# uac.net
KiCad netlist of a schematic drawn in EAGLE
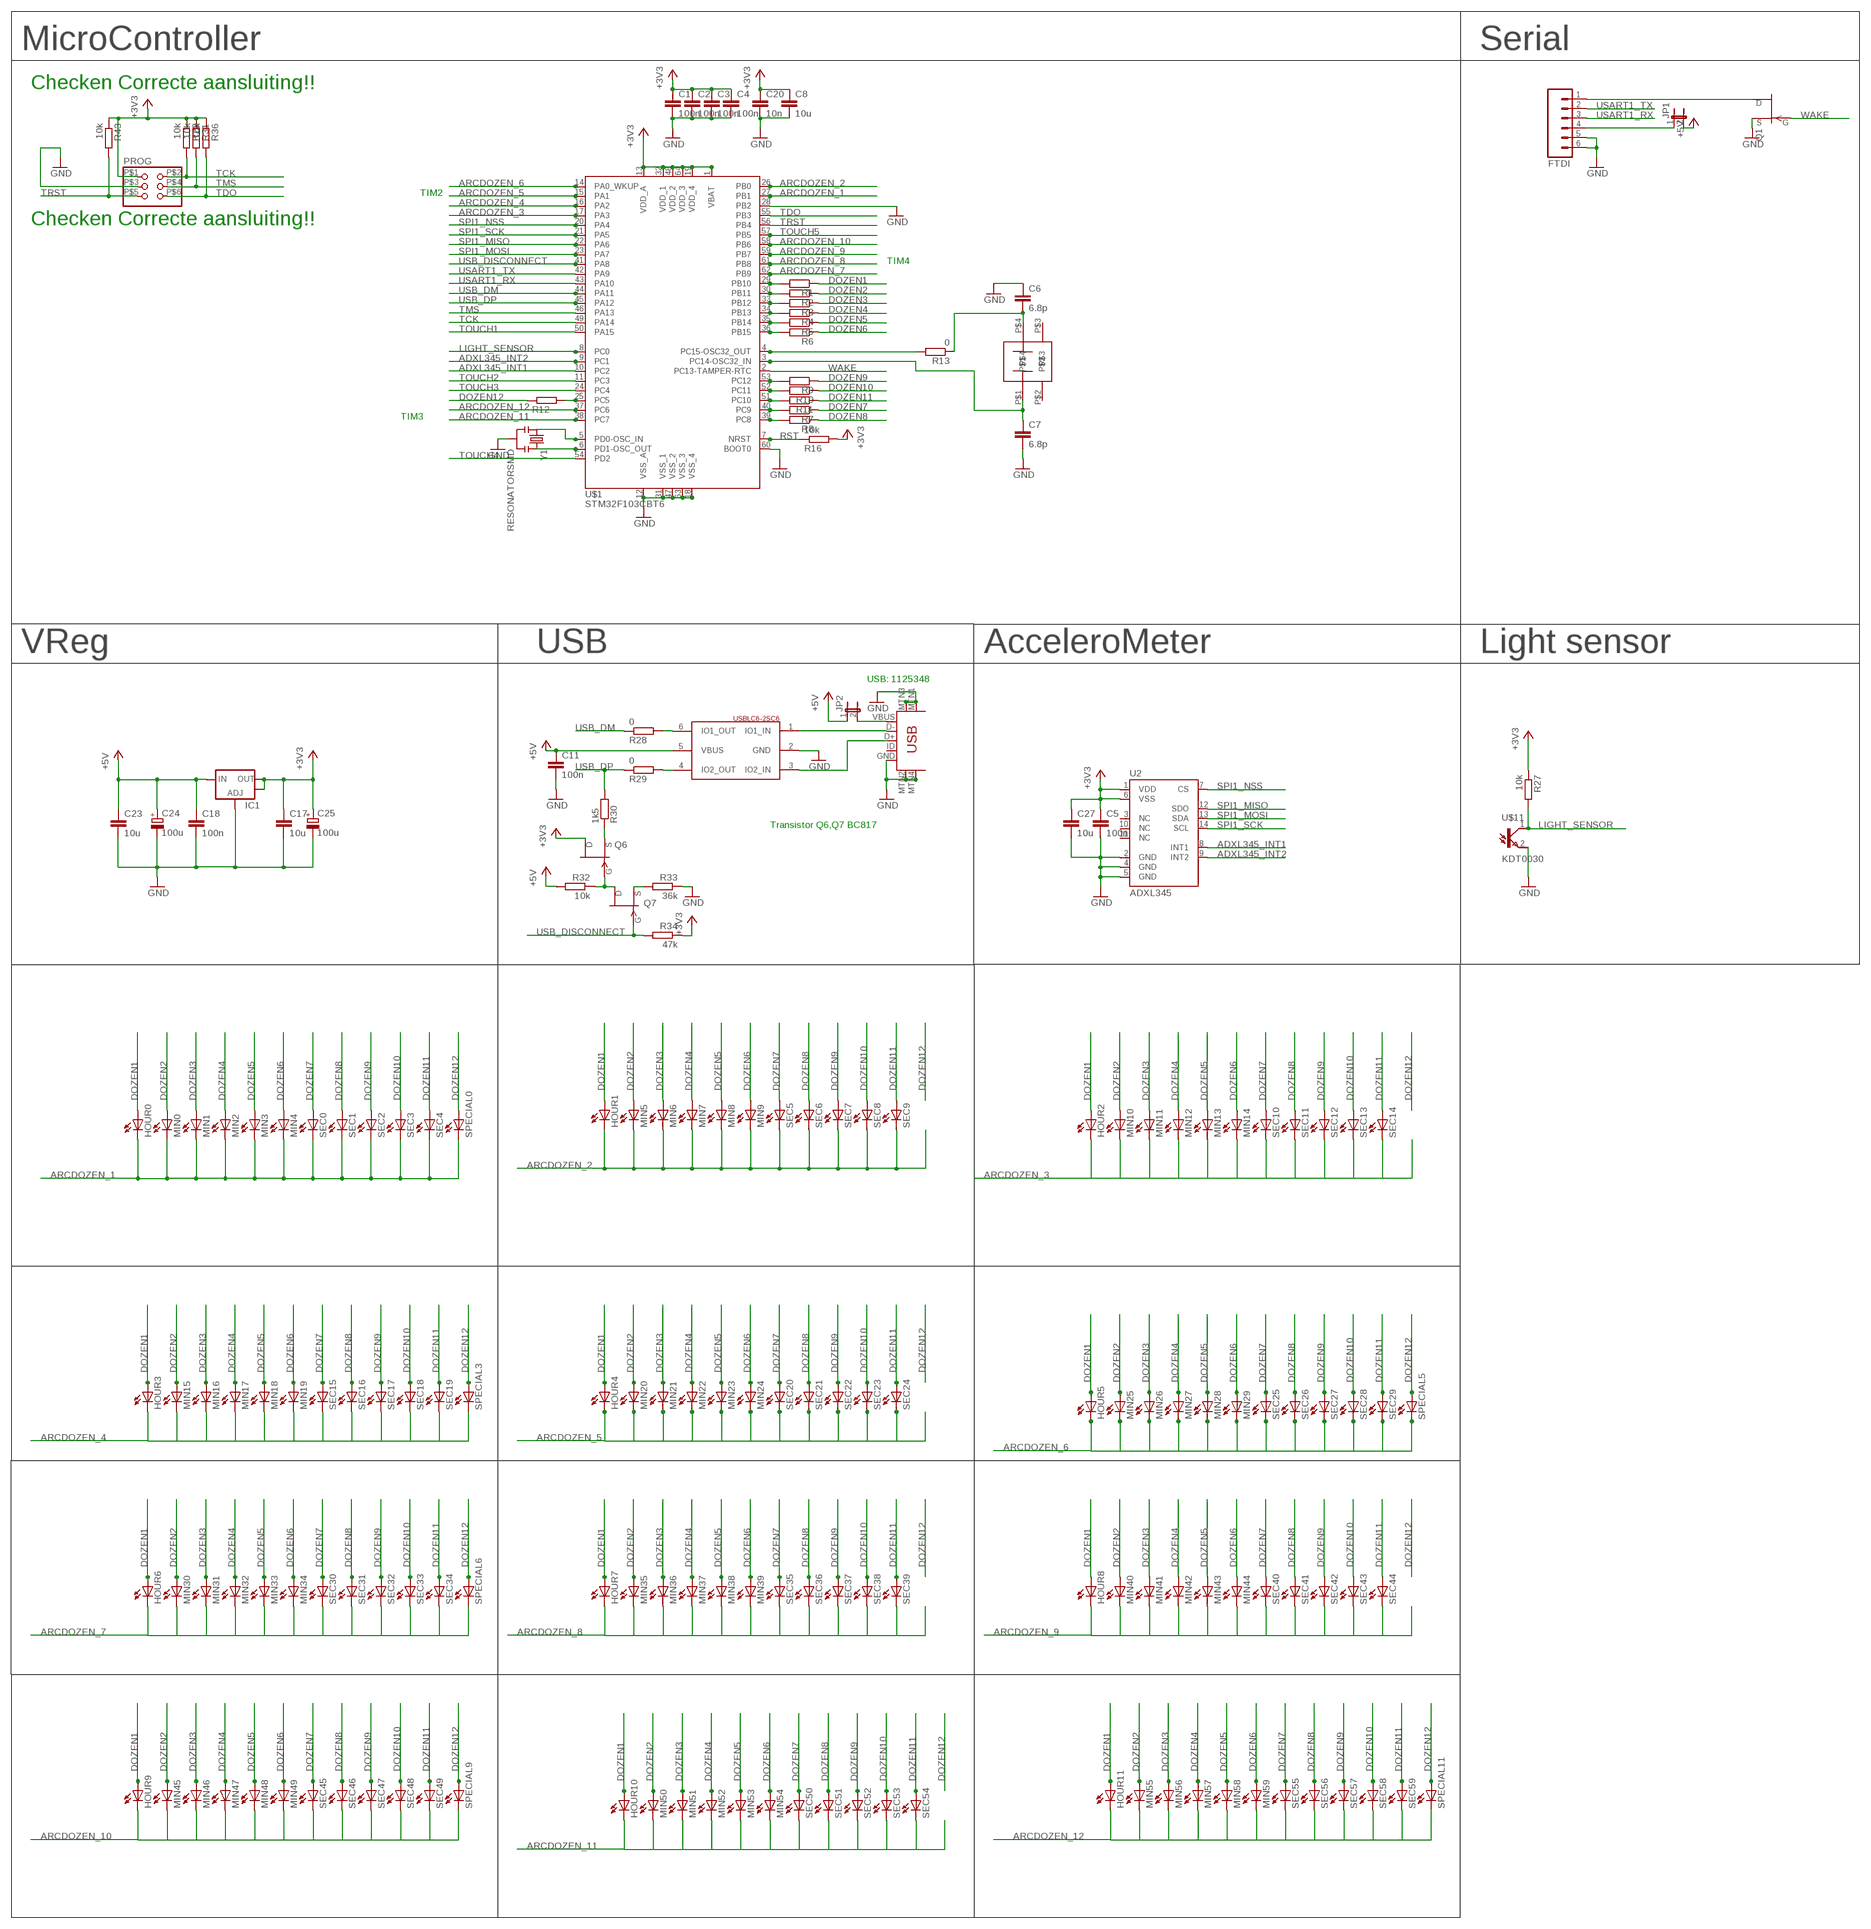
[diagram p0: schematic, sheet 1]

(export (version "E")
  (design (tool "Eeschema 10.0.6"))
  (components
    (comp (ref "C1")
      (value "100n")
      (footprint "eagle-import:C0603")
      (libsource (lib "eagle-import") (part "C-EUC0603"))
    )
    (comp (ref "C2")
      (value "100n")
      (footprint "eagle-import:C0603")
      (libsource (lib "eagle-import") (part "C-EUC0603"))
    )
    (comp (ref "C3")
      (value "100n")
      (footprint "eagle-import:C0603")
      (libsource (lib "eagle-import") (part "C-EUC0603"))
    )
    (comp (ref "C4")
      (value "100n")
      (footprint "eagle-import:C0603")
      (libsource (lib "eagle-import") (part "C-EUC0603"))
    )
    (comp (ref "C5")
      (value "100n")
      (footprint "eagle-import:C0603")
      (libsource (lib "eagle-import") (part "C-EUC0603"))
    )
    (comp (ref "C6")
      (value "6.8p")
      (footprint "eagle-import:C0603")
      (libsource (lib "eagle-import") (part "C-EUC0603"))
    )
    (comp (ref "C7")
      (value "6.8p")
      (footprint "eagle-import:C0603")
      (libsource (lib "eagle-import") (part "C-EUC0603"))
    )
    (comp (ref "C8")
      (value "10u")
      (footprint "eagle-import:C0603")
      (libsource (lib "eagle-import") (part "C-EUC0603"))
    )
    (comp (ref "C11")
      (value "100n")
      (footprint "eagle-import:C0603")
      (libsource (lib "eagle-import") (part "C-EUC0603"))
    )
    (comp (ref "C17")
      (value "10u")
      (footprint "eagle-import:C0603")
      (libsource (lib "eagle-import") (part "C-EUC0603"))
    )
    (comp (ref "C18")
      (value "100n")
      (footprint "eagle-import:C0603")
      (libsource (lib "eagle-import") (part "C-EUC0603"))
    )
    (comp (ref "C20")
      (value "10n")
      (footprint "eagle-import:C0603")
      (libsource (lib "eagle-import") (part "C-EUC0603"))
    )
    (comp (ref "C23")
      (value "10u")
      (footprint "eagle-import:C0603")
      (libsource (lib "eagle-import") (part "C-EUC0603"))
    )
    (comp (ref "C24")
      (value "100u")
      (footprint "eagle-import:SMC_C")
      (libsource (lib "eagle-import") (part "CPOL-EUSMCC"))
    )
    (comp (ref "C25")
      (value "100u")
      (footprint "eagle-import:SMC_C")
      (libsource (lib "eagle-import") (part "CPOL-EUSMCC"))
    )
    (comp (ref "C27")
      (value "10u")
      (footprint "eagle-import:C0603")
      (libsource (lib "eagle-import") (part "C-EUC0603"))
    )
    (comp (ref "FTDI")
      (value "M06SMD")
      (footprint "eagle-import:1X06-SMD")
      (libsource (lib "eagle-import") (part "M06SMD"))
    )
    (comp (ref "HOUR0")
      (value "LEDCHIPLED_0603")
      (footprint "eagle-import:CHIPLED_0603")
      (libsource (lib "eagle-import") (part "LEDCHIPLED_0603"))
    )
    (comp (ref "HOUR1")
      (value "LEDCHIPLED_0603")
      (footprint "eagle-import:CHIPLED_0603")
      (libsource (lib "eagle-import") (part "LEDCHIPLED_0603"))
    )
    (comp (ref "HOUR2")
      (value "LEDCHIPLED_0603")
      (footprint "eagle-import:CHIPLED_0603")
      (libsource (lib "eagle-import") (part "LEDCHIPLED_0603"))
    )
    (comp (ref "HOUR3")
      (value "LEDCHIPLED_0603")
      (footprint "eagle-import:CHIPLED_0603")
      (libsource (lib "eagle-import") (part "LEDCHIPLED_0603"))
    )
    (comp (ref "HOUR4")
      (value "LEDCHIPLED_0603")
      (footprint "eagle-import:CHIPLED_0603")
      (libsource (lib "eagle-import") (part "LEDCHIPLED_0603"))
    )
    (comp (ref "HOUR5")
      (value "LEDCHIPLED_0603")
      (footprint "eagle-import:CHIPLED_0603")
      (libsource (lib "eagle-import") (part "LEDCHIPLED_0603"))
    )
    (comp (ref "HOUR6")
      (value "LEDCHIPLED_0603")
      (footprint "eagle-import:CHIPLED_0603")
      (libsource (lib "eagle-import") (part "LEDCHIPLED_0603"))
    )
    (comp (ref "HOUR7")
      (value "LEDCHIPLED_0603")
      (footprint "eagle-import:CHIPLED_0603")
      (libsource (lib "eagle-import") (part "LEDCHIPLED_0603"))
    )
    (comp (ref "HOUR8")
      (value "LEDCHIPLED_0603")
      (footprint "eagle-import:CHIPLED_0603")
      (libsource (lib "eagle-import") (part "LEDCHIPLED_0603"))
    )
    (comp (ref "HOUR9")
      (value "LEDCHIPLED_0603")
      (footprint "eagle-import:CHIPLED_0603")
      (libsource (lib "eagle-import") (part "LEDCHIPLED_0603"))
    )
    (comp (ref "HOUR10")
      (value "LEDCHIPLED_0603")
      (footprint "eagle-import:CHIPLED_0603")
      (libsource (lib "eagle-import") (part "LEDCHIPLED_0603"))
    )
    (comp (ref "HOUR11")
      (value "LEDCHIPLED_0603")
      (footprint "eagle-import:CHIPLED_0603")
      (libsource (lib "eagle-import") (part "LEDCHIPLED_0603"))
    )
    (comp (ref "IC1")
      (value "V_REG_LM1117SOT223")
      (footprint "eagle-import:SOT223")
      (libsource (lib "eagle-import") (part "V_REG_LM1117SOT223"))
    )
    (comp (ref "JP1")
      (value "JUMPER-2SMD-NO")
      (footprint "eagle-import:SJ_2S-NO")
      (libsource (lib "eagle-import") (part "JUMPER-2SMD-NO"))
    )
    (comp (ref "JP2")
      (value "JUMPER-2SMD-NO")
      (footprint "eagle-import:SJ_2S-NO")
      (libsource (lib "eagle-import") (part "JUMPER-2SMD-NO"))
    )
    (comp (ref "MIN0")
      (value "LEDCHIPLED_0603")
      (footprint "eagle-import:CHIPLED_0603")
      (libsource (lib "eagle-import") (part "LEDCHIPLED_0603"))
    )
    (comp (ref "MIN1")
      (value "LEDCHIPLED_0603")
      (footprint "eagle-import:CHIPLED_0603")
      (libsource (lib "eagle-import") (part "LEDCHIPLED_0603"))
    )
    (comp (ref "MIN2")
      (value "LEDCHIPLED_0603")
      (footprint "eagle-import:CHIPLED_0603")
      (libsource (lib "eagle-import") (part "LEDCHIPLED_0603"))
    )
    (comp (ref "MIN3")
      (value "LEDCHIPLED_0603")
      (footprint "eagle-import:CHIPLED_0603")
      (libsource (lib "eagle-import") (part "LEDCHIPLED_0603"))
    )
    (comp (ref "MIN4")
      (value "LEDCHIPLED_0603")
      (footprint "eagle-import:CHIPLED_0603")
      (libsource (lib "eagle-import") (part "LEDCHIPLED_0603"))
    )
    (comp (ref "MIN5")
      (value "LEDCHIPLED_0603")
      (footprint "eagle-import:CHIPLED_0603")
      (libsource (lib "eagle-import") (part "LEDCHIPLED_0603"))
    )
    (comp (ref "MIN6")
      (value "LEDCHIPLED_0603")
      (footprint "eagle-import:CHIPLED_0603")
      (libsource (lib "eagle-import") (part "LEDCHIPLED_0603"))
    )
    (comp (ref "MIN7")
      (value "LEDCHIPLED_0603")
      (footprint "eagle-import:CHIPLED_0603")
      (libsource (lib "eagle-import") (part "LEDCHIPLED_0603"))
    )
    (comp (ref "MIN8")
      (value "LEDCHIPLED_0603")
      (footprint "eagle-import:CHIPLED_0603")
      (libsource (lib "eagle-import") (part "LEDCHIPLED_0603"))
    )
    (comp (ref "MIN9")
      (value "LEDCHIPLED_0603")
      (footprint "eagle-import:CHIPLED_0603")
      (libsource (lib "eagle-import") (part "LEDCHIPLED_0603"))
    )
    (comp (ref "MIN10")
      (value "LEDCHIPLED_0603")
      (footprint "eagle-import:CHIPLED_0603")
      (libsource (lib "eagle-import") (part "LEDCHIPLED_0603"))
    )
    (comp (ref "MIN11")
      (value "LEDCHIPLED_0603")
      (footprint "eagle-import:CHIPLED_0603")
      (libsource (lib "eagle-import") (part "LEDCHIPLED_0603"))
    )
    (comp (ref "MIN12")
      (value "LEDCHIPLED_0603")
      (footprint "eagle-import:CHIPLED_0603")
      (libsource (lib "eagle-import") (part "LEDCHIPLED_0603"))
    )
    (comp (ref "MIN13")
      (value "LEDCHIPLED_0603")
      (footprint "eagle-import:CHIPLED_0603")
      (libsource (lib "eagle-import") (part "LEDCHIPLED_0603"))
    )
    (comp (ref "MIN14")
      (value "LEDCHIPLED_0603")
      (footprint "eagle-import:CHIPLED_0603")
      (libsource (lib "eagle-import") (part "LEDCHIPLED_0603"))
    )
    (comp (ref "MIN15")
      (value "LEDCHIPLED_0603")
      (footprint "eagle-import:CHIPLED_0603")
      (libsource (lib "eagle-import") (part "LEDCHIPLED_0603"))
    )
    (comp (ref "MIN16")
      (value "LEDCHIPLED_0603")
      (footprint "eagle-import:CHIPLED_0603")
      (libsource (lib "eagle-import") (part "LEDCHIPLED_0603"))
    )
    (comp (ref "MIN17")
      (value "LEDCHIPLED_0603")
      (footprint "eagle-import:CHIPLED_0603")
      (libsource (lib "eagle-import") (part "LEDCHIPLED_0603"))
    )
    (comp (ref "MIN18")
      (value "LEDCHIPLED_0603")
      (footprint "eagle-import:CHIPLED_0603")
      (libsource (lib "eagle-import") (part "LEDCHIPLED_0603"))
    )
    (comp (ref "MIN19")
      (value "LEDCHIPLED_0603")
      (footprint "eagle-import:CHIPLED_0603")
      (libsource (lib "eagle-import") (part "LEDCHIPLED_0603"))
    )
    (comp (ref "MIN20")
      (value "LEDCHIPLED_0603")
      (footprint "eagle-import:CHIPLED_0603")
      (libsource (lib "eagle-import") (part "LEDCHIPLED_0603"))
    )
    (comp (ref "MIN21")
      (value "LEDCHIPLED_0603")
      (footprint "eagle-import:CHIPLED_0603")
      (libsource (lib "eagle-import") (part "LEDCHIPLED_0603"))
    )
    (comp (ref "MIN22")
      (value "LEDCHIPLED_0603")
      (footprint "eagle-import:CHIPLED_0603")
      (libsource (lib "eagle-import") (part "LEDCHIPLED_0603"))
    )
    (comp (ref "MIN23")
      (value "LEDCHIPLED_0603")
      (footprint "eagle-import:CHIPLED_0603")
      (libsource (lib "eagle-import") (part "LEDCHIPLED_0603"))
    )
    (comp (ref "MIN24")
      (value "LEDCHIPLED_0603")
      (footprint "eagle-import:CHIPLED_0603")
      (libsource (lib "eagle-import") (part "LEDCHIPLED_0603"))
    )
    (comp (ref "MIN25")
      (value "LEDCHIPLED_0603")
      (footprint "eagle-import:CHIPLED_0603")
      (libsource (lib "eagle-import") (part "LEDCHIPLED_0603"))
    )
    (comp (ref "MIN26")
      (value "LEDCHIPLED_0603")
      (footprint "eagle-import:CHIPLED_0603")
      (libsource (lib "eagle-import") (part "LEDCHIPLED_0603"))
    )
    (comp (ref "MIN27")
      (value "LEDCHIPLED_0603")
      (footprint "eagle-import:CHIPLED_0603")
      (libsource (lib "eagle-import") (part "LEDCHIPLED_0603"))
    )
    (comp (ref "MIN28")
      (value "LEDCHIPLED_0603")
      (footprint "eagle-import:CHIPLED_0603")
      (libsource (lib "eagle-import") (part "LEDCHIPLED_0603"))
    )
    (comp (ref "MIN29")
      (value "LEDCHIPLED_0603")
      (footprint "eagle-import:CHIPLED_0603")
      (libsource (lib "eagle-import") (part "LEDCHIPLED_0603"))
    )
    (comp (ref "MIN30")
      (value "LEDCHIPLED_0603")
      (footprint "eagle-import:CHIPLED_0603")
      (libsource (lib "eagle-import") (part "LEDCHIPLED_0603"))
    )
    (comp (ref "MIN31")
      (value "LEDCHIPLED_0603")
      (footprint "eagle-import:CHIPLED_0603")
      (libsource (lib "eagle-import") (part "LEDCHIPLED_0603"))
    )
    (comp (ref "MIN32")
      (value "LEDCHIPLED_0603")
      (footprint "eagle-import:CHIPLED_0603")
      (libsource (lib "eagle-import") (part "LEDCHIPLED_0603"))
    )
    (comp (ref "MIN33")
      (value "LEDCHIPLED_0603")
      (footprint "eagle-import:CHIPLED_0603")
      (libsource (lib "eagle-import") (part "LEDCHIPLED_0603"))
    )
    (comp (ref "MIN34")
      (value "LEDCHIPLED_0603")
      (footprint "eagle-import:CHIPLED_0603")
      (libsource (lib "eagle-import") (part "LEDCHIPLED_0603"))
    )
    (comp (ref "MIN35")
      (value "LEDCHIPLED_0603")
      (footprint "eagle-import:CHIPLED_0603")
      (libsource (lib "eagle-import") (part "LEDCHIPLED_0603"))
    )
    (comp (ref "MIN36")
      (value "LEDCHIPLED_0603")
      (footprint "eagle-import:CHIPLED_0603")
      (libsource (lib "eagle-import") (part "LEDCHIPLED_0603"))
    )
    (comp (ref "MIN37")
      (value "LEDCHIPLED_0603")
      (footprint "eagle-import:CHIPLED_0603")
      (libsource (lib "eagle-import") (part "LEDCHIPLED_0603"))
    )
    (comp (ref "MIN38")
      (value "LEDCHIPLED_0603")
      (footprint "eagle-import:CHIPLED_0603")
      (libsource (lib "eagle-import") (part "LEDCHIPLED_0603"))
    )
    (comp (ref "MIN39")
      (value "LEDCHIPLED_0603")
      (footprint "eagle-import:CHIPLED_0603")
      (libsource (lib "eagle-import") (part "LEDCHIPLED_0603"))
    )
    (comp (ref "MIN40")
      (value "LEDCHIPLED_0603")
      (footprint "eagle-import:CHIPLED_0603")
      (libsource (lib "eagle-import") (part "LEDCHIPLED_0603"))
    )
    (comp (ref "MIN41")
      (value "LEDCHIPLED_0603")
      (footprint "eagle-import:CHIPLED_0603")
      (libsource (lib "eagle-import") (part "LEDCHIPLED_0603"))
    )
    (comp (ref "MIN42")
      (value "LEDCHIPLED_0603")
      (footprint "eagle-import:CHIPLED_0603")
      (libsource (lib "eagle-import") (part "LEDCHIPLED_0603"))
    )
    (comp (ref "MIN43")
      (value "LEDCHIPLED_0603")
      (footprint "eagle-import:CHIPLED_0603")
      (libsource (lib "eagle-import") (part "LEDCHIPLED_0603"))
    )
    (comp (ref "MIN44")
      (value "LEDCHIPLED_0603")
      (footprint "eagle-import:CHIPLED_0603")
      (libsource (lib "eagle-import") (part "LEDCHIPLED_0603"))
    )
    (comp (ref "MIN45")
      (value "LEDCHIPLED_0603")
      (footprint "eagle-import:CHIPLED_0603")
      (libsource (lib "eagle-import") (part "LEDCHIPLED_0603"))
    )
    (comp (ref "MIN46")
      (value "LEDCHIPLED_0603")
      (footprint "eagle-import:CHIPLED_0603")
      (libsource (lib "eagle-import") (part "LEDCHIPLED_0603"))
    )
    (comp (ref "MIN47")
      (value "LEDCHIPLED_0603")
      (footprint "eagle-import:CHIPLED_0603")
      (libsource (lib "eagle-import") (part "LEDCHIPLED_0603"))
    )
    (comp (ref "MIN48")
      (value "LEDCHIPLED_0603")
      (footprint "eagle-import:CHIPLED_0603")
      (libsource (lib "eagle-import") (part "LEDCHIPLED_0603"))
    )
    (comp (ref "MIN49")
      (value "LEDCHIPLED_0603")
      (footprint "eagle-import:CHIPLED_0603")
      (libsource (lib "eagle-import") (part "LEDCHIPLED_0603"))
    )
    (comp (ref "MIN50")
      (value "LEDCHIPLED_0603")
      (footprint "eagle-import:CHIPLED_0603")
      (libsource (lib "eagle-import") (part "LEDCHIPLED_0603"))
    )
    (comp (ref "MIN51")
      (value "LEDCHIPLED_0603")
      (footprint "eagle-import:CHIPLED_0603")
      (libsource (lib "eagle-import") (part "LEDCHIPLED_0603"))
    )
    (comp (ref "MIN52")
      (value "LEDCHIPLED_0603")
      (footprint "eagle-import:CHIPLED_0603")
      (libsource (lib "eagle-import") (part "LEDCHIPLED_0603"))
    )
    (comp (ref "MIN53")
      (value "LEDCHIPLED_0603")
      (footprint "eagle-import:CHIPLED_0603")
      (libsource (lib "eagle-import") (part "LEDCHIPLED_0603"))
    )
    (comp (ref "MIN54")
      (value "LEDCHIPLED_0603")
      (footprint "eagle-import:CHIPLED_0603")
      (libsource (lib "eagle-import") (part "LEDCHIPLED_0603"))
    )
    (comp (ref "MIN55")
      (value "LEDCHIPLED_0603")
      (footprint "eagle-import:CHIPLED_0603")
      (libsource (lib "eagle-import") (part "LEDCHIPLED_0603"))
    )
    (comp (ref "MIN56")
      (value "LEDCHIPLED_0603")
      (footprint "eagle-import:CHIPLED_0603")
      (libsource (lib "eagle-import") (part "LEDCHIPLED_0603"))
    )
    (comp (ref "MIN57")
      (value "LEDCHIPLED_0603")
      (footprint "eagle-import:CHIPLED_0603")
      (libsource (lib "eagle-import") (part "LEDCHIPLED_0603"))
    )
    (comp (ref "MIN58")
      (value "LEDCHIPLED_0603")
      (footprint "eagle-import:CHIPLED_0603")
      (libsource (lib "eagle-import") (part "LEDCHIPLED_0603"))
    )
    (comp (ref "MIN59")
      (value "LEDCHIPLED_0603")
      (footprint "eagle-import:CHIPLED_0603")
      (libsource (lib "eagle-import") (part "LEDCHIPLED_0603"))
    )
    (comp (ref "PROG")
      (value "PINHD-2X3SMT")
      (footprint "eagle-import:2X03_SMT")
      (libsource (lib "eagle-import") (part "PINHD-2X3SMT"))
    )
    (comp (ref "Q1")
      (value "2N7002CK4SST")
      (footprint "eagle-import:SOT23")
      (libsource (lib "eagle-import") (part "2N7002CKSST4"))
    )
    (comp (ref "Q6")
      (value "2N7002CK4SST")
      (footprint "eagle-import:SOT23")
      (libsource (lib "eagle-import") (part "2N7002CKSST4"))
    )
    (comp (ref "Q7")
      (value "2N7002CK4SST")
      (footprint "eagle-import:SOT23")
      (libsource (lib "eagle-import") (part "2N7002CKSST4"))
    )
    (comp (ref "R1")
      (value "R-EU_R0603")
      (footprint "eagle-import:R0603")
      (libsource (lib "eagle-import") (part "R-EU_R0603"))
    )
    (comp (ref "R2")
      (value "R-EU_R0603")
      (footprint "eagle-import:R0603")
      (libsource (lib "eagle-import") (part "R-EU_R0603"))
    )
    (comp (ref "R3")
      (value "R-EU_R0603")
      (footprint "eagle-import:R0603")
      (libsource (lib "eagle-import") (part "R-EU_R0603"))
    )
    (comp (ref "R4")
      (value "R-EU_R0603")
      (footprint "eagle-import:R0603")
      (libsource (lib "eagle-import") (part "R-EU_R0603"))
    )
    (comp (ref "R5")
      (value "R-EU_R0603")
      (footprint "eagle-import:R0603")
      (libsource (lib "eagle-import") (part "R-EU_R0603"))
    )
    (comp (ref "R6")
      (value "R-EU_R0603")
      (footprint "eagle-import:R0603")
      (libsource (lib "eagle-import") (part "R-EU_R0603"))
    )
    (comp (ref "R7")
      (value "R-EU_R0603")
      (footprint "eagle-import:R0603")
      (libsource (lib "eagle-import") (part "R-EU_R0603"))
    )
    (comp (ref "R8")
      (value "R-EU_R0603")
      (footprint "eagle-import:R0603")
      (libsource (lib "eagle-import") (part "R-EU_R0603"))
    )
    (comp (ref "R9")
      (value "R-EU_R0603")
      (footprint "eagle-import:R0603")
      (libsource (lib "eagle-import") (part "R-EU_R0603"))
    )
    (comp (ref "R10")
      (value "R-EU_R0603")
      (footprint "eagle-import:R0603")
      (libsource (lib "eagle-import") (part "R-EU_R0603"))
    )
    (comp (ref "R11")
      (value "R-EU_R0603")
      (footprint "eagle-import:R0603")
      (libsource (lib "eagle-import") (part "R-EU_R0603"))
    )
    (comp (ref "R12")
      (value "R-EU_R0603")
      (footprint "eagle-import:R0603")
      (libsource (lib "eagle-import") (part "R-EU_R0603"))
    )
    (comp (ref "R13")
      (value "0")
      (footprint "eagle-import:R0603")
      (libsource (lib "eagle-import") (part "R-EU_R0603"))
    )
    (comp (ref "R16")
      (value "10k")
      (footprint "eagle-import:R0603")
      (libsource (lib "eagle-import") (part "R-EU_R0603"))
    )
    (comp (ref "R23")
      (value "10k")
      (footprint "eagle-import:R0603")
      (libsource (lib "eagle-import") (part "R-EU_R0603"))
    )
    (comp (ref "R27")
      (value "10k")
      (footprint "eagle-import:R0603")
      (libsource (lib "eagle-import") (part "R-EU_R0603"))
    )
    (comp (ref "R28")
      (value "0")
      (footprint "eagle-import:R0603")
      (libsource (lib "eagle-import") (part "R-EU_R0603"))
    )
    (comp (ref "R29")
      (value "0")
      (footprint "eagle-import:R0603")
      (libsource (lib "eagle-import") (part "R-EU_R0603"))
    )
    (comp (ref "R30")
      (value "1k5")
      (footprint "eagle-import:R0603")
      (libsource (lib "eagle-import") (part "R-EU_R0603"))
    )
    (comp (ref "R31")
      (value "10k")
      (footprint "eagle-import:R0603")
      (libsource (lib "eagle-import") (part "R-EU_R0603"))
    )
    (comp (ref "R32")
      (value "10k")
      (footprint "eagle-import:R0603")
      (libsource (lib "eagle-import") (part "R-EU_R0603"))
    )
    (comp (ref "R33")
      (value "36k")
      (footprint "eagle-import:R0603")
      (libsource (lib "eagle-import") (part "R-EU_R0603"))
    )
    (comp (ref "R34")
      (value "47k")
      (footprint "eagle-import:R0603")
      (libsource (lib "eagle-import") (part "R-EU_R0603"))
    )
    (comp (ref "R36")
      (value "10k")
      (footprint "eagle-import:R0603")
      (libsource (lib "eagle-import") (part "R-EU_R0603"))
    )
    (comp (ref "R43")
      (value "10k")
      (footprint "eagle-import:R0603")
      (libsource (lib "eagle-import") (part "R-EU_R0603"))
    )
    (comp (ref "SEC0")
      (value "LEDCHIPLED_0603")
      (footprint "eagle-import:CHIPLED_0603")
      (libsource (lib "eagle-import") (part "LEDCHIPLED_0603"))
    )
    (comp (ref "SEC1")
      (value "LEDCHIPLED_0603")
      (footprint "eagle-import:CHIPLED_0603")
      (libsource (lib "eagle-import") (part "LEDCHIPLED_0603"))
    )
    (comp (ref "SEC2")
      (value "LEDCHIPLED_0603")
      (footprint "eagle-import:CHIPLED_0603")
      (libsource (lib "eagle-import") (part "LEDCHIPLED_0603"))
    )
    (comp (ref "SEC3")
      (value "LEDCHIPLED_0603")
      (footprint "eagle-import:CHIPLED_0603")
      (libsource (lib "eagle-import") (part "LEDCHIPLED_0603"))
    )
    (comp (ref "SEC4")
      (value "LEDCHIPLED_0603")
      (footprint "eagle-import:CHIPLED_0603")
      (libsource (lib "eagle-import") (part "LEDCHIPLED_0603"))
    )
    (comp (ref "SEC5")
      (value "LEDCHIPLED_0603")
      (footprint "eagle-import:CHIPLED_0603")
      (libsource (lib "eagle-import") (part "LEDCHIPLED_0603"))
    )
    (comp (ref "SEC6")
      (value "LEDCHIPLED_0603")
      (footprint "eagle-import:CHIPLED_0603")
      (libsource (lib "eagle-import") (part "LEDCHIPLED_0603"))
    )
    (comp (ref "SEC7")
      (value "LEDCHIPLED_0603")
      (footprint "eagle-import:CHIPLED_0603")
      (libsource (lib "eagle-import") (part "LEDCHIPLED_0603"))
    )
    (comp (ref "SEC8")
      (value "LEDCHIPLED_0603")
      (footprint "eagle-import:CHIPLED_0603")
      (libsource (lib "eagle-import") (part "LEDCHIPLED_0603"))
    )
    (comp (ref "SEC9")
      (value "LEDCHIPLED_0603")
      (footprint "eagle-import:CHIPLED_0603")
      (libsource (lib "eagle-import") (part "LEDCHIPLED_0603"))
    )
    (comp (ref "SEC10")
      (value "LEDCHIPLED_0603")
      (footprint "eagle-import:CHIPLED_0603")
      (libsource (lib "eagle-import") (part "LEDCHIPLED_0603"))
    )
    (comp (ref "SEC11")
      (value "LEDCHIPLED_0603")
      (footprint "eagle-import:CHIPLED_0603")
      (libsource (lib "eagle-import") (part "LEDCHIPLED_0603"))
    )
    (comp (ref "SEC12")
      (value "LEDCHIPLED_0603")
      (footprint "eagle-import:CHIPLED_0603")
      (libsource (lib "eagle-import") (part "LEDCHIPLED_0603"))
    )
    (comp (ref "SEC13")
      (value "LEDCHIPLED_0603")
      (footprint "eagle-import:CHIPLED_0603")
      (libsource (lib "eagle-import") (part "LEDCHIPLED_0603"))
    )
    (comp (ref "SEC14")
      (value "LEDCHIPLED_0603")
      (footprint "eagle-import:CHIPLED_0603")
      (libsource (lib "eagle-import") (part "LEDCHIPLED_0603"))
    )
    (comp (ref "SEC15")
      (value "LEDCHIPLED_0603")
      (footprint "eagle-import:CHIPLED_0603")
      (libsource (lib "eagle-import") (part "LEDCHIPLED_0603"))
    )
    (comp (ref "SEC16")
      (value "LEDCHIPLED_0603")
      (footprint "eagle-import:CHIPLED_0603")
      (libsource (lib "eagle-import") (part "LEDCHIPLED_0603"))
    )
    (comp (ref "SEC17")
      (value "LEDCHIPLED_0603")
      (footprint "eagle-import:CHIPLED_0603")
      (libsource (lib "eagle-import") (part "LEDCHIPLED_0603"))
    )
    (comp (ref "SEC18")
      (value "LEDCHIPLED_0603")
      (footprint "eagle-import:CHIPLED_0603")
      (libsource (lib "eagle-import") (part "LEDCHIPLED_0603"))
    )
    (comp (ref "SEC19")
      (value "LEDCHIPLED_0603")
      (footprint "eagle-import:CHIPLED_0603")
      (libsource (lib "eagle-import") (part "LEDCHIPLED_0603"))
    )
    (comp (ref "SEC20")
      (value "LEDCHIPLED_0603")
      (footprint "eagle-import:CHIPLED_0603")
      (libsource (lib "eagle-import") (part "LEDCHIPLED_0603"))
    )
    (comp (ref "SEC21")
      (value "LEDCHIPLED_0603")
      (footprint "eagle-import:CHIPLED_0603")
      (libsource (lib "eagle-import") (part "LEDCHIPLED_0603"))
    )
    (comp (ref "SEC22")
      (value "LEDCHIPLED_0603")
      (footprint "eagle-import:CHIPLED_0603")
      (libsource (lib "eagle-import") (part "LEDCHIPLED_0603"))
    )
    (comp (ref "SEC23")
      (value "LEDCHIPLED_0603")
      (footprint "eagle-import:CHIPLED_0603")
      (libsource (lib "eagle-import") (part "LEDCHIPLED_0603"))
    )
    (comp (ref "SEC24")
      (value "LEDCHIPLED_0603")
      (footprint "eagle-import:CHIPLED_0603")
      (libsource (lib "eagle-import") (part "LEDCHIPLED_0603"))
    )
    (comp (ref "SEC25")
      (value "LEDCHIPLED_0603")
      (footprint "eagle-import:CHIPLED_0603")
      (libsource (lib "eagle-import") (part "LEDCHIPLED_0603"))
    )
    (comp (ref "SEC26")
      (value "LEDCHIPLED_0603")
      (footprint "eagle-import:CHIPLED_0603")
      (libsource (lib "eagle-import") (part "LEDCHIPLED_0603"))
    )
    (comp (ref "SEC27")
      (value "LEDCHIPLED_0603")
      (footprint "eagle-import:CHIPLED_0603")
      (libsource (lib "eagle-import") (part "LEDCHIPLED_0603"))
    )
    (comp (ref "SEC28")
      (value "LEDCHIPLED_0603")
      (footprint "eagle-import:CHIPLED_0603")
      (libsource (lib "eagle-import") (part "LEDCHIPLED_0603"))
    )
    (comp (ref "SEC29")
      (value "LEDCHIPLED_0603")
      (footprint "eagle-import:CHIPLED_0603")
      (libsource (lib "eagle-import") (part "LEDCHIPLED_0603"))
    )
    (comp (ref "SEC30")
      (value "LEDCHIPLED_0603")
      (footprint "eagle-import:CHIPLED_0603")
      (libsource (lib "eagle-import") (part "LEDCHIPLED_0603"))
    )
    (comp (ref "SEC31")
      (value "LEDCHIPLED_0603")
      (footprint "eagle-import:CHIPLED_0603")
      (libsource (lib "eagle-import") (part "LEDCHIPLED_0603"))
    )
    (comp (ref "SEC32")
      (value "LEDCHIPLED_0603")
      (footprint "eagle-import:CHIPLED_0603")
      (libsource (lib "eagle-import") (part "LEDCHIPLED_0603"))
    )
    (comp (ref "SEC33")
      (value "LEDCHIPLED_0603")
      (footprint "eagle-import:CHIPLED_0603")
      (libsource (lib "eagle-import") (part "LEDCHIPLED_0603"))
    )
    (comp (ref "SEC34")
      (value "LEDCHIPLED_0603")
      (footprint "eagle-import:CHIPLED_0603")
      (libsource (lib "eagle-import") (part "LEDCHIPLED_0603"))
    )
    (comp (ref "SEC35")
      (value "LEDCHIPLED_0603")
      (footprint "eagle-import:CHIPLED_0603")
      (libsource (lib "eagle-import") (part "LEDCHIPLED_0603"))
    )
    (comp (ref "SEC36")
      (value "LEDCHIPLED_0603")
      (footprint "eagle-import:CHIPLED_0603")
      (libsource (lib "eagle-import") (part "LEDCHIPLED_0603"))
    )
    (comp (ref "SEC37")
      (value "LEDCHIPLED_0603")
      (footprint "eagle-import:CHIPLED_0603")
      (libsource (lib "eagle-import") (part "LEDCHIPLED_0603"))
    )
    (comp (ref "SEC38")
      (value "LEDCHIPLED_0603")
      (footprint "eagle-import:CHIPLED_0603")
      (libsource (lib "eagle-import") (part "LEDCHIPLED_0603"))
    )
    (comp (ref "SEC39")
      (value "LEDCHIPLED_0603")
      (footprint "eagle-import:CHIPLED_0603")
      (libsource (lib "eagle-import") (part "LEDCHIPLED_0603"))
    )
    (comp (ref "SEC40")
      (value "LEDCHIPLED_0603")
      (footprint "eagle-import:CHIPLED_0603")
      (libsource (lib "eagle-import") (part "LEDCHIPLED_0603"))
    )
    (comp (ref "SEC41")
      (value "LEDCHIPLED_0603")
      (footprint "eagle-import:CHIPLED_0603")
      (libsource (lib "eagle-import") (part "LEDCHIPLED_0603"))
    )
    (comp (ref "SEC42")
      (value "LEDCHIPLED_0603")
      (footprint "eagle-import:CHIPLED_0603")
      (libsource (lib "eagle-import") (part "LEDCHIPLED_0603"))
    )
    (comp (ref "SEC43")
      (value "LEDCHIPLED_0603")
      (footprint "eagle-import:CHIPLED_0603")
      (libsource (lib "eagle-import") (part "LEDCHIPLED_0603"))
    )
    (comp (ref "SEC44")
      (value "LEDCHIPLED_0603")
      (footprint "eagle-import:CHIPLED_0603")
      (libsource (lib "eagle-import") (part "LEDCHIPLED_0603"))
    )
    (comp (ref "SEC45")
      (value "LEDCHIPLED_0603")
      (footprint "eagle-import:CHIPLED_0603")
      (libsource (lib "eagle-import") (part "LEDCHIPLED_0603"))
    )
    (comp (ref "SEC46")
      (value "LEDCHIPLED_0603")
      (footprint "eagle-import:CHIPLED_0603")
      (libsource (lib "eagle-import") (part "LEDCHIPLED_0603"))
    )
    (comp (ref "SEC47")
      (value "LEDCHIPLED_0603")
      (footprint "eagle-import:CHIPLED_0603")
      (libsource (lib "eagle-import") (part "LEDCHIPLED_0603"))
    )
    (comp (ref "SEC48")
      (value "LEDCHIPLED_0603")
      (footprint "eagle-import:CHIPLED_0603")
      (libsource (lib "eagle-import") (part "LEDCHIPLED_0603"))
    )
    (comp (ref "SEC49")
      (value "LEDCHIPLED_0603")
      (footprint "eagle-import:CHIPLED_0603")
      (libsource (lib "eagle-import") (part "LEDCHIPLED_0603"))
    )
    (comp (ref "SEC50")
      (value "LEDCHIPLED_0603")
      (footprint "eagle-import:CHIPLED_0603")
      (libsource (lib "eagle-import") (part "LEDCHIPLED_0603"))
    )
    (comp (ref "SEC51")
      (value "LEDCHIPLED_0603")
      (footprint "eagle-import:CHIPLED_0603")
      (libsource (lib "eagle-import") (part "LEDCHIPLED_0603"))
    )
    (comp (ref "SEC52")
      (value "LEDCHIPLED_0603")
      (footprint "eagle-import:CHIPLED_0603")
      (libsource (lib "eagle-import") (part "LEDCHIPLED_0603"))
    )
    (comp (ref "SEC53")
      (value "LEDCHIPLED_0603")
      (footprint "eagle-import:CHIPLED_0603")
      (libsource (lib "eagle-import") (part "LEDCHIPLED_0603"))
    )
    (comp (ref "SEC54")
      (value "LEDCHIPLED_0603")
      (footprint "eagle-import:CHIPLED_0603")
      (libsource (lib "eagle-import") (part "LEDCHIPLED_0603"))
    )
    (comp (ref "SEC55")
      (value "LEDCHIPLED_0603")
      (footprint "eagle-import:CHIPLED_0603")
      (libsource (lib "eagle-import") (part "LEDCHIPLED_0603"))
    )
    (comp (ref "SEC56")
      (value "LEDCHIPLED_0603")
      (footprint "eagle-import:CHIPLED_0603")
      (libsource (lib "eagle-import") (part "LEDCHIPLED_0603"))
    )
    (comp (ref "SEC57")
      (value "LEDCHIPLED_0603")
      (footprint "eagle-import:CHIPLED_0603")
      (libsource (lib "eagle-import") (part "LEDCHIPLED_0603"))
    )
    (comp (ref "SEC58")
      (value "LEDCHIPLED_0603")
      (footprint "eagle-import:CHIPLED_0603")
      (libsource (lib "eagle-import") (part "LEDCHIPLED_0603"))
    )
    (comp (ref "SEC59")
      (value "LEDCHIPLED_0603")
      (footprint "eagle-import:CHIPLED_0603")
      (libsource (lib "eagle-import") (part "LEDCHIPLED_0603"))
    )
    (comp (ref "SPECIAL0")
      (value "LEDCHIPLED_0603")
      (footprint "eagle-import:CHIPLED_0603")
      (libsource (lib "eagle-import") (part "LEDCHIPLED_0603"))
    )
    (comp (ref "SPECIAL3")
      (value "LEDCHIPLED_0603")
      (footprint "eagle-import:CHIPLED_0603")
      (libsource (lib "eagle-import") (part "LEDCHIPLED_0603"))
    )
    (comp (ref "SPECIAL5")
      (value "LEDCHIPLED_0603")
      (footprint "eagle-import:CHIPLED_0603")
      (libsource (lib "eagle-import") (part "LEDCHIPLED_0603"))
    )
    (comp (ref "SPECIAL6")
      (value "LEDCHIPLED_0603")
      (footprint "eagle-import:CHIPLED_0603")
      (libsource (lib "eagle-import") (part "LEDCHIPLED_0603"))
    )
    (comp (ref "SPECIAL9")
      (value "LEDCHIPLED_0603")
      (footprint "eagle-import:CHIPLED_0603")
      (libsource (lib "eagle-import") (part "LEDCHIPLED_0603"))
    )
    (comp (ref "SPECIAL11")
      (value "LEDCHIPLED_0603")
      (footprint "eagle-import:CHIPLED_0603")
      (libsource (lib "eagle-import") (part "LEDCHIPLED_0603"))
    )
    (comp (ref "U$1")
      (value "STM32F103CBT6")
      (footprint "eagle-import:LQFP64")
      (libsource (lib "eagle-import") (part "STM32F103CBT6"))
    )
    (comp (ref "U$2")
      (value "CRYSTAL_32KHZ")
      (footprint "eagle-import:CRYSTAL_32KHZ")
      (fields (field (name "MPN") "MC-306 32.768K-E3:ROHS"))
      (libsource (lib "eagle-import") (part "CRYSTAL_32KHZ"))
    )
    (comp (ref "U$11")
      (value "KDT0030")
      (footprint "eagle-import:FLD00030")
      (fields (field (name "MPN") "KDT00030TR"))
      (libsource (lib "eagle-import") (part "KDT0030"))
    )
    (comp (ref "U$12")
      (value "USB-MINIB-5PIN")
      (footprint "eagle-import:USB-MINIB")
      (libsource (lib "eagle-import") (part "USB-MINIB-5PIN"))
    )
    (comp (ref "U$13")
      (value "USBLC6-2SC6")
      (footprint "eagle-import:SOT23")
      (libsource (lib "eagle-import") (part "USBLC6-2SC6"))
    )
    (comp (ref "U2")
      (value "ADXL345")
      (footprint "eagle-import:LGA14")
      (libsource (lib "eagle-import") (part "ADXL345"))
    )
    (comp (ref "Y1")
      (value "RESONATORSMD")
      (footprint "eagle-import:RESONATOR-SMD")
      (libsource (lib "eagle-import") (part "RESONATORSMD"))
    )
  )
  (nets
    (net (code "1") (name "+3V3") (class "Default")
      (node (ref "C1") (pin "1") (pinfunction "1_1") (pintype "passive"))
      (node (ref "C17") (pin "1") (pinfunction "1_1") (pintype "passive"))
      (node (ref "C2") (pin "1") (pinfunction "1_1") (pintype "passive"))
      (node (ref "C20") (pin "1") (pinfunction "1_1") (pintype "passive"))
      (node (ref "C25") (pin "+") (pinfunction "+_+") (pintype "passive"))
      (node (ref "C27") (pin "1") (pinfunction "1_1") (pintype "passive"))
      (node (ref "C3") (pin "1") (pinfunction "1_1") (pintype "passive"))
      (node (ref "C4") (pin "1") (pinfunction "1_1") (pintype "passive"))
      (node (ref "C5") (pin "1") (pinfunction "1_1") (pintype "passive"))
      (node (ref "C8") (pin "1") (pinfunction "1_1") (pintype "passive"))
      (node (ref "IC1") (pin "2") (pinfunction "OUT_2") (pintype "output"))
      (node (ref "IC1") (pin "4") (pinfunction "OUT_4") (pintype "output"))
      (node (ref "PROG") (pin "P$1") (pinfunction "1_P$1") (pintype "passive"))
      (node (ref "Q6") (pin "3") (pinfunction "D_3") (pintype "passive"))
      (node (ref "R16") (pin "2") (pinfunction "2_2") (pintype "passive"))
      (node (ref "R23") (pin "1") (pinfunction "1_1") (pintype "passive"))
      (node (ref "R27") (pin "1") (pinfunction "1_1") (pintype "passive"))
      (node (ref "R31") (pin "1") (pinfunction "1_1") (pintype "passive"))
      (node (ref "R34") (pin "1") (pinfunction "1_1") (pintype "passive"))
      (node (ref "R36") (pin "1") (pinfunction "1_1") (pintype "passive"))
      (node (ref "R43") (pin "1") (pinfunction "1_1") (pintype "passive"))
      (node (ref "U$1") (pin "1") (pinfunction "VBAT_1") (pintype "power_in"))
      (node (ref "U$1") (pin "13") (pinfunction "VDD_A_13") (pintype "power_in"))
      (node (ref "U$1") (pin "19") (pinfunction "VDD_4_19") (pintype "power_in"))
      (node (ref "U$1") (pin "32") (pinfunction "VDD_1_32") (pintype "power_in"))
      (node (ref "U$1") (pin "48") (pinfunction "VDD_2_48") (pintype "power_in"))
      (node (ref "U$1") (pin "64") (pinfunction "VDD_3_64") (pintype "power_in"))
      (node (ref "U2") (pin "1") (pinfunction "VDD_1") (pintype "bidirectional"))
      (node (ref "U2") (pin "6") (pinfunction "VSS_6") (pintype "bidirectional"))
    )
    (net (code "2") (name "+5V") (class "Default")
      (node (ref "C11") (pin "1") (pinfunction "1_1") (pintype "passive"))
      (node (ref "C18") (pin "1") (pinfunction "1_1") (pintype "passive"))
      (node (ref "C23") (pin "1") (pinfunction "1_1") (pintype "passive"))
      (node (ref "C24") (pin "+") (pinfunction "+_+") (pintype "passive"))
      (node (ref "IC1") (pin "3") (pinfunction "IN_3") (pintype "input"))
      (node (ref "JP1") (pin "2") (pinfunction "2_2") (pintype "passive"))
      (node (ref "JP2") (pin "1") (pinfunction "1_1") (pintype "passive"))
      (node (ref "R32") (pin "2") (pinfunction "2_2") (pintype "passive"))
      (node (ref "U$13") (pin "5") (pinfunction "VBUS_5") (pintype "bidirectional"))
    )
    (net (code "3") (name "/ADXL345_INT1") (class "Default")
      (node (ref "U$1") (pin "10") (pinfunction "PC2_10") (pintype "bidirectional"))
      (node (ref "U2") (pin "8") (pinfunction "INT1_8") (pintype "bidirectional"))
    )
    (net (code "4") (name "/ADXL345_INT2") (class "Default")
      (node (ref "U$1") (pin "9") (pinfunction "PC1_9") (pintype "bidirectional"))
      (node (ref "U2") (pin "9") (pinfunction "INT2_9") (pintype "bidirectional"))
    )
    (net (code "5") (name "/ARCDOZEN_1") (class "Default")
      (node (ref "HOUR0") (pin "C") (pinfunction "C_C") (pintype "passive"))
      (node (ref "MIN0") (pin "C") (pinfunction "C_C") (pintype "passive"))
      (node (ref "MIN1") (pin "C") (pinfunction "C_C") (pintype "passive"))
      (node (ref "MIN2") (pin "C") (pinfunction "C_C") (pintype "passive"))
      (node (ref "MIN3") (pin "C") (pinfunction "C_C") (pintype "passive"))
      (node (ref "MIN4") (pin "C") (pinfunction "C_C") (pintype "passive"))
      (node (ref "SEC0") (pin "C") (pinfunction "C_C") (pintype "passive"))
      (node (ref "SEC1") (pin "C") (pinfunction "C_C") (pintype "passive"))
      (node (ref "SEC2") (pin "C") (pinfunction "C_C") (pintype "passive"))
      (node (ref "SEC3") (pin "C") (pinfunction "C_C") (pintype "passive"))
      (node (ref "SEC4") (pin "C") (pinfunction "C_C") (pintype "passive"))
      (node (ref "SPECIAL0") (pin "C") (pinfunction "C_C") (pintype "passive"))
      (node (ref "U$1") (pin "27") (pinfunction "PB1_27") (pintype "bidirectional"))
    )
    (net (code "6") (name "/ARCDOZEN_2") (class "Default")
      (node (ref "HOUR1") (pin "C") (pinfunction "C_C") (pintype "passive"))
      (node (ref "MIN5") (pin "C") (pinfunction "C_C") (pintype "passive"))
      (node (ref "MIN6") (pin "C") (pinfunction "C_C") (pintype "passive"))
      (node (ref "MIN7") (pin "C") (pinfunction "C_C") (pintype "passive"))
      (node (ref "MIN8") (pin "C") (pinfunction "C_C") (pintype "passive"))
      (node (ref "MIN9") (pin "C") (pinfunction "C_C") (pintype "passive"))
      (node (ref "SEC5") (pin "C") (pinfunction "C_C") (pintype "passive"))
      (node (ref "SEC6") (pin "C") (pinfunction "C_C") (pintype "passive"))
      (node (ref "SEC7") (pin "C") (pinfunction "C_C") (pintype "passive"))
      (node (ref "SEC8") (pin "C") (pinfunction "C_C") (pintype "passive"))
      (node (ref "SEC9") (pin "C") (pinfunction "C_C") (pintype "passive"))
      (node (ref "U$1") (pin "26") (pinfunction "PB0_26") (pintype "bidirectional"))
    )
    (net (code "7") (name "/ARCDOZEN_3") (class "Default")
      (node (ref "HOUR2") (pin "C") (pinfunction "C_C") (pintype "passive"))
      (node (ref "MIN10") (pin "C") (pinfunction "C_C") (pintype "passive"))
      (node (ref "MIN11") (pin "C") (pinfunction "C_C") (pintype "passive"))
      (node (ref "MIN12") (pin "C") (pinfunction "C_C") (pintype "passive"))
      (node (ref "MIN13") (pin "C") (pinfunction "C_C") (pintype "passive"))
      (node (ref "MIN14") (pin "C") (pinfunction "C_C") (pintype "passive"))
      (node (ref "SEC10") (pin "C") (pinfunction "C_C") (pintype "passive"))
      (node (ref "SEC11") (pin "C") (pinfunction "C_C") (pintype "passive"))
      (node (ref "SEC12") (pin "C") (pinfunction "C_C") (pintype "passive"))
      (node (ref "SEC13") (pin "C") (pinfunction "C_C") (pintype "passive"))
      (node (ref "SEC14") (pin "C") (pinfunction "C_C") (pintype "passive"))
      (node (ref "U$1") (pin "17") (pinfunction "PA3_17") (pintype "bidirectional"))
    )
    (net (code "8") (name "/ARCDOZEN_4") (class "Default")
      (node (ref "HOUR3") (pin "C") (pinfunction "C_C") (pintype "passive"))
      (node (ref "MIN15") (pin "C") (pinfunction "C_C") (pintype "passive"))
      (node (ref "MIN16") (pin "C") (pinfunction "C_C") (pintype "passive"))
      (node (ref "MIN17") (pin "C") (pinfunction "C_C") (pintype "passive"))
      (node (ref "MIN18") (pin "C") (pinfunction "C_C") (pintype "passive"))
      (node (ref "MIN19") (pin "C") (pinfunction "C_C") (pintype "passive"))
      (node (ref "SEC15") (pin "C") (pinfunction "C_C") (pintype "passive"))
      (node (ref "SEC16") (pin "C") (pinfunction "C_C") (pintype "passive"))
      (node (ref "SEC17") (pin "C") (pinfunction "C_C") (pintype "passive"))
      (node (ref "SEC18") (pin "C") (pinfunction "C_C") (pintype "passive"))
      (node (ref "SEC19") (pin "C") (pinfunction "C_C") (pintype "passive"))
      (node (ref "SPECIAL3") (pin "C") (pinfunction "C_C") (pintype "passive"))
      (node (ref "U$1") (pin "16") (pinfunction "PA2_16") (pintype "bidirectional"))
    )
    (net (code "9") (name "/ARCDOZEN_5") (class "Default")
      (node (ref "HOUR4") (pin "C") (pinfunction "C_C") (pintype "passive"))
      (node (ref "MIN20") (pin "C") (pinfunction "C_C") (pintype "passive"))
      (node (ref "MIN21") (pin "C") (pinfunction "C_C") (pintype "passive"))
      (node (ref "MIN22") (pin "C") (pinfunction "C_C") (pintype "passive"))
      (node (ref "MIN23") (pin "C") (pinfunction "C_C") (pintype "passive"))
      (node (ref "MIN24") (pin "C") (pinfunction "C_C") (pintype "passive"))
      (node (ref "SEC20") (pin "C") (pinfunction "C_C") (pintype "passive"))
      (node (ref "SEC21") (pin "C") (pinfunction "C_C") (pintype "passive"))
      (node (ref "SEC22") (pin "C") (pinfunction "C_C") (pintype "passive"))
      (node (ref "SEC23") (pin "C") (pinfunction "C_C") (pintype "passive"))
      (node (ref "SEC24") (pin "C") (pinfunction "C_C") (pintype "passive"))
      (node (ref "U$1") (pin "15") (pinfunction "PA1_15") (pintype "bidirectional"))
    )
    (net (code "10") (name "/ARCDOZEN_6") (class "Default")
      (node (ref "HOUR5") (pin "C") (pinfunction "C_C") (pintype "passive"))
      (node (ref "MIN25") (pin "C") (pinfunction "C_C") (pintype "passive"))
      (node (ref "MIN26") (pin "C") (pinfunction "C_C") (pintype "passive"))
      (node (ref "MIN27") (pin "C") (pinfunction "C_C") (pintype "passive"))
      (node (ref "MIN28") (pin "C") (pinfunction "C_C") (pintype "passive"))
      (node (ref "MIN29") (pin "C") (pinfunction "C_C") (pintype "passive"))
      (node (ref "SEC25") (pin "C") (pinfunction "C_C") (pintype "passive"))
      (node (ref "SEC26") (pin "C") (pinfunction "C_C") (pintype "passive"))
      (node (ref "SEC27") (pin "C") (pinfunction "C_C") (pintype "passive"))
      (node (ref "SEC28") (pin "C") (pinfunction "C_C") (pintype "passive"))
      (node (ref "SEC29") (pin "C") (pinfunction "C_C") (pintype "passive"))
      (node (ref "SPECIAL5") (pin "C") (pinfunction "C_C") (pintype "passive"))
      (node (ref "U$1") (pin "14") (pinfunction "PA0_WKUP_14") (pintype "bidirectional"))
    )
    (net (code "11") (name "/ARCDOZEN_7") (class "Default")
      (node (ref "HOUR6") (pin "C") (pinfunction "C_C") (pintype "passive"))
      (node (ref "MIN30") (pin "C") (pinfunction "C_C") (pintype "passive"))
      (node (ref "MIN31") (pin "C") (pinfunction "C_C") (pintype "passive"))
      (node (ref "MIN32") (pin "C") (pinfunction "C_C") (pintype "passive"))
      (node (ref "MIN33") (pin "C") (pinfunction "C_C") (pintype "passive"))
      (node (ref "MIN34") (pin "C") (pinfunction "C_C") (pintype "passive"))
      (node (ref "SEC30") (pin "C") (pinfunction "C_C") (pintype "passive"))
      (node (ref "SEC31") (pin "C") (pinfunction "C_C") (pintype "passive"))
      (node (ref "SEC32") (pin "C") (pinfunction "C_C") (pintype "passive"))
      (node (ref "SEC33") (pin "C") (pinfunction "C_C") (pintype "passive"))
      (node (ref "SEC34") (pin "C") (pinfunction "C_C") (pintype "passive"))
      (node (ref "SPECIAL6") (pin "C") (pinfunction "C_C") (pintype "passive"))
      (node (ref "U$1") (pin "62") (pinfunction "PB9_62") (pintype "input"))
    )
    (net (code "12") (name "/ARCDOZEN_8") (class "Default")
      (node (ref "HOUR7") (pin "C") (pinfunction "C_C") (pintype "passive"))
      (node (ref "MIN35") (pin "C") (pinfunction "C_C") (pintype "passive"))
      (node (ref "MIN36") (pin "C") (pinfunction "C_C") (pintype "passive"))
      (node (ref "MIN37") (pin "C") (pinfunction "C_C") (pintype "passive"))
      (node (ref "MIN38") (pin "C") (pinfunction "C_C") (pintype "passive"))
      (node (ref "MIN39") (pin "C") (pinfunction "C_C") (pintype "passive"))
      (node (ref "SEC35") (pin "C") (pinfunction "C_C") (pintype "passive"))
      (node (ref "SEC36") (pin "C") (pinfunction "C_C") (pintype "passive"))
      (node (ref "SEC37") (pin "C") (pinfunction "C_C") (pintype "passive"))
      (node (ref "SEC38") (pin "C") (pinfunction "C_C") (pintype "passive"))
      (node (ref "SEC39") (pin "C") (pinfunction "C_C") (pintype "passive"))
      (node (ref "U$1") (pin "61") (pinfunction "PB8_61") (pintype "bidirectional"))
    )
    (net (code "13") (name "/ARCDOZEN_9") (class "Default")
      (node (ref "HOUR8") (pin "C") (pinfunction "C_C") (pintype "passive"))
      (node (ref "MIN40") (pin "C") (pinfunction "C_C") (pintype "passive"))
      (node (ref "MIN41") (pin "C") (pinfunction "C_C") (pintype "passive"))
      (node (ref "MIN42") (pin "C") (pinfunction "C_C") (pintype "passive"))
      (node (ref "MIN43") (pin "C") (pinfunction "C_C") (pintype "passive"))
      (node (ref "MIN44") (pin "C") (pinfunction "C_C") (pintype "passive"))
      (node (ref "SEC40") (pin "C") (pinfunction "C_C") (pintype "passive"))
      (node (ref "SEC41") (pin "C") (pinfunction "C_C") (pintype "passive"))
      (node (ref "SEC42") (pin "C") (pinfunction "C_C") (pintype "passive"))
      (node (ref "SEC43") (pin "C") (pinfunction "C_C") (pintype "passive"))
      (node (ref "SEC44") (pin "C") (pinfunction "C_C") (pintype "passive"))
      (node (ref "U$1") (pin "59") (pinfunction "PB7_59") (pintype "bidirectional"))
    )
    (net (code "14") (name "/ARCDOZEN_10") (class "Default")
      (node (ref "HOUR9") (pin "C") (pinfunction "C_C") (pintype "passive"))
      (node (ref "MIN45") (pin "C") (pinfunction "C_C") (pintype "passive"))
      (node (ref "MIN46") (pin "C") (pinfunction "C_C") (pintype "passive"))
      (node (ref "MIN47") (pin "C") (pinfunction "C_C") (pintype "passive"))
      (node (ref "MIN48") (pin "C") (pinfunction "C_C") (pintype "passive"))
      (node (ref "MIN49") (pin "C") (pinfunction "C_C") (pintype "passive"))
      (node (ref "SEC45") (pin "C") (pinfunction "C_C") (pintype "passive"))
      (node (ref "SEC46") (pin "C") (pinfunction "C_C") (pintype "passive"))
      (node (ref "SEC47") (pin "C") (pinfunction "C_C") (pintype "passive"))
      (node (ref "SEC48") (pin "C") (pinfunction "C_C") (pintype "passive"))
      (node (ref "SEC49") (pin "C") (pinfunction "C_C") (pintype "passive"))
      (node (ref "SPECIAL9") (pin "C") (pinfunction "C_C") (pintype "passive"))
      (node (ref "U$1") (pin "58") (pinfunction "PB6_58") (pintype "input"))
    )
    (net (code "15") (name "/ARCDOZEN_11") (class "Default")
      (node (ref "HOUR10") (pin "C") (pinfunction "C_C") (pintype "passive"))
      (node (ref "MIN50") (pin "C") (pinfunction "C_C") (pintype "passive"))
      (node (ref "MIN51") (pin "C") (pinfunction "C_C") (pintype "passive"))
      (node (ref "MIN52") (pin "C") (pinfunction "C_C") (pintype "passive"))
      (node (ref "MIN53") (pin "C") (pinfunction "C_C") (pintype "passive"))
      (node (ref "MIN54") (pin "C") (pinfunction "C_C") (pintype "passive"))
      (node (ref "SEC50") (pin "C") (pinfunction "C_C") (pintype "passive"))
      (node (ref "SEC51") (pin "C") (pinfunction "C_C") (pintype "passive"))
      (node (ref "SEC52") (pin "C") (pinfunction "C_C") (pintype "passive"))
      (node (ref "SEC53") (pin "C") (pinfunction "C_C") (pintype "passive"))
      (node (ref "SEC54") (pin "C") (pinfunction "C_C") (pintype "passive"))
      (node (ref "U$1") (pin "38") (pinfunction "PC7_38") (pintype "bidirectional"))
    )
    (net (code "16") (name "/ARCDOZEN_12") (class "Default")
      (node (ref "HOUR11") (pin "C") (pinfunction "C_C") (pintype "passive"))
      (node (ref "MIN55") (pin "C") (pinfunction "C_C") (pintype "passive"))
      (node (ref "MIN56") (pin "C") (pinfunction "C_C") (pintype "passive"))
      (node (ref "MIN57") (pin "C") (pinfunction "C_C") (pintype "passive"))
      (node (ref "MIN58") (pin "C") (pinfunction "C_C") (pintype "passive"))
      (node (ref "MIN59") (pin "C") (pinfunction "C_C") (pintype "passive"))
      (node (ref "SEC55") (pin "C") (pinfunction "C_C") (pintype "passive"))
      (node (ref "SEC56") (pin "C") (pinfunction "C_C") (pintype "passive"))
      (node (ref "SEC57") (pin "C") (pinfunction "C_C") (pintype "passive"))
      (node (ref "SEC58") (pin "C") (pinfunction "C_C") (pintype "passive"))
      (node (ref "SEC59") (pin "C") (pinfunction "C_C") (pintype "passive"))
      (node (ref "SPECIAL11") (pin "C") (pinfunction "C_C") (pintype "passive"))
      (node (ref "U$1") (pin "37") (pinfunction "PC6_37") (pintype "bidirectional"))
    )
    (net (code "17") (name "/DOZEN1") (class "Default")
      (node (ref "HOUR0") (pin "A") (pinfunction "A_A") (pintype "passive"))
      (node (ref "HOUR1") (pin "A") (pinfunction "A_A") (pintype "passive"))
      (node (ref "HOUR10") (pin "A") (pinfunction "A_A") (pintype "passive"))
      (node (ref "HOUR11") (pin "A") (pinfunction "A_A") (pintype "passive"))
      (node (ref "HOUR2") (pin "A") (pinfunction "A_A") (pintype "passive"))
      (node (ref "HOUR3") (pin "A") (pinfunction "A_A") (pintype "passive"))
      (node (ref "HOUR4") (pin "A") (pinfunction "A_A") (pintype "passive"))
      (node (ref "HOUR5") (pin "A") (pinfunction "A_A") (pintype "passive"))
      (node (ref "HOUR6") (pin "A") (pinfunction "A_A") (pintype "passive"))
      (node (ref "HOUR7") (pin "A") (pinfunction "A_A") (pintype "passive"))
      (node (ref "HOUR8") (pin "A") (pinfunction "A_A") (pintype "passive"))
      (node (ref "HOUR9") (pin "A") (pinfunction "A_A") (pintype "passive"))
      (node (ref "R1") (pin "1") (pinfunction "1_1") (pintype "passive"))
    )
    (net (code "18") (name "/DOZEN2") (class "Default")
      (node (ref "MIN0") (pin "A") (pinfunction "A_A") (pintype "passive"))
      (node (ref "MIN10") (pin "A") (pinfunction "A_A") (pintype "passive"))
      (node (ref "MIN15") (pin "A") (pinfunction "A_A") (pintype "passive"))
      (node (ref "MIN20") (pin "A") (pinfunction "A_A") (pintype "passive"))
      (node (ref "MIN25") (pin "A") (pinfunction "A_A") (pintype "passive"))
      (node (ref "MIN30") (pin "A") (pinfunction "A_A") (pintype "passive"))
      (node (ref "MIN35") (pin "A") (pinfunction "A_A") (pintype "passive"))
      (node (ref "MIN40") (pin "A") (pinfunction "A_A") (pintype "passive"))
      (node (ref "MIN45") (pin "A") (pinfunction "A_A") (pintype "passive"))
      (node (ref "MIN5") (pin "A") (pinfunction "A_A") (pintype "passive"))
      (node (ref "MIN50") (pin "A") (pinfunction "A_A") (pintype "passive"))
      (node (ref "MIN55") (pin "A") (pinfunction "A_A") (pintype "passive"))
      (node (ref "R2") (pin "1") (pinfunction "1_1") (pintype "passive"))
    )
    (net (code "19") (name "/DOZEN3") (class "Default")
      (node (ref "MIN1") (pin "A") (pinfunction "A_A") (pintype "passive"))
      (node (ref "MIN11") (pin "A") (pinfunction "A_A") (pintype "passive"))
      (node (ref "MIN16") (pin "A") (pinfunction "A_A") (pintype "passive"))
      (node (ref "MIN21") (pin "A") (pinfunction "A_A") (pintype "passive"))
      (node (ref "MIN26") (pin "A") (pinfunction "A_A") (pintype "passive"))
      (node (ref "MIN31") (pin "A") (pinfunction "A_A") (pintype "passive"))
      (node (ref "MIN36") (pin "A") (pinfunction "A_A") (pintype "passive"))
      (node (ref "MIN41") (pin "A") (pinfunction "A_A") (pintype "passive"))
      (node (ref "MIN46") (pin "A") (pinfunction "A_A") (pintype "passive"))
      (node (ref "MIN51") (pin "A") (pinfunction "A_A") (pintype "passive"))
      (node (ref "MIN56") (pin "A") (pinfunction "A_A") (pintype "passive"))
      (node (ref "MIN6") (pin "A") (pinfunction "A_A") (pintype "passive"))
      (node (ref "R3") (pin "1") (pinfunction "1_1") (pintype "passive"))
    )
    (net (code "20") (name "/DOZEN4") (class "Default")
      (node (ref "MIN12") (pin "A") (pinfunction "A_A") (pintype "passive"))
      (node (ref "MIN17") (pin "A") (pinfunction "A_A") (pintype "passive"))
      (node (ref "MIN2") (pin "A") (pinfunction "A_A") (pintype "passive"))
      (node (ref "MIN22") (pin "A") (pinfunction "A_A") (pintype "passive"))
      (node (ref "MIN27") (pin "A") (pinfunction "A_A") (pintype "passive"))
      (node (ref "MIN32") (pin "A") (pinfunction "A_A") (pintype "passive"))
      (node (ref "MIN37") (pin "A") (pinfunction "A_A") (pintype "passive"))
      (node (ref "MIN42") (pin "A") (pinfunction "A_A") (pintype "passive"))
      (node (ref "MIN47") (pin "A") (pinfunction "A_A") (pintype "passive"))
      (node (ref "MIN52") (pin "A") (pinfunction "A_A") (pintype "passive"))
      (node (ref "MIN57") (pin "A") (pinfunction "A_A") (pintype "passive"))
      (node (ref "MIN7") (pin "A") (pinfunction "A_A") (pintype "passive"))
      (node (ref "R4") (pin "1") (pinfunction "1_1") (pintype "passive"))
    )
    (net (code "21") (name "/DOZEN5") (class "Default")
      (node (ref "MIN13") (pin "A") (pinfunction "A_A") (pintype "passive"))
      (node (ref "MIN18") (pin "A") (pinfunction "A_A") (pintype "passive"))
      (node (ref "MIN23") (pin "A") (pinfunction "A_A") (pintype "passive"))
      (node (ref "MIN28") (pin "A") (pinfunction "A_A") (pintype "passive"))
      (node (ref "MIN3") (pin "A") (pinfunction "A_A") (pintype "passive"))
      (node (ref "MIN33") (pin "A") (pinfunction "A_A") (pintype "passive"))
      (node (ref "MIN38") (pin "A") (pinfunction "A_A") (pintype "passive"))
      (node (ref "MIN43") (pin "A") (pinfunction "A_A") (pintype "passive"))
      (node (ref "MIN48") (pin "A") (pinfunction "A_A") (pintype "passive"))
      (node (ref "MIN53") (pin "A") (pinfunction "A_A") (pintype "passive"))
      (node (ref "MIN58") (pin "A") (pinfunction "A_A") (pintype "passive"))
      (node (ref "MIN8") (pin "A") (pinfunction "A_A") (pintype "passive"))
      (node (ref "R5") (pin "1") (pinfunction "1_1") (pintype "passive"))
    )
    (net (code "22") (name "/DOZEN6") (class "Default")
      (node (ref "MIN14") (pin "A") (pinfunction "A_A") (pintype "passive"))
      (node (ref "MIN19") (pin "A") (pinfunction "A_A") (pintype "passive"))
      (node (ref "MIN24") (pin "A") (pinfunction "A_A") (pintype "passive"))
      (node (ref "MIN29") (pin "A") (pinfunction "A_A") (pintype "passive"))
      (node (ref "MIN34") (pin "A") (pinfunction "A_A") (pintype "passive"))
      (node (ref "MIN39") (pin "A") (pinfunction "A_A") (pintype "passive"))
      (node (ref "MIN4") (pin "A") (pinfunction "A_A") (pintype "passive"))
      (node (ref "MIN44") (pin "A") (pinfunction "A_A") (pintype "passive"))
      (node (ref "MIN49") (pin "A") (pinfunction "A_A") (pintype "passive"))
      (node (ref "MIN54") (pin "A") (pinfunction "A_A") (pintype "passive"))
      (node (ref "MIN59") (pin "A") (pinfunction "A_A") (pintype "passive"))
      (node (ref "MIN9") (pin "A") (pinfunction "A_A") (pintype "passive"))
      (node (ref "R6") (pin "1") (pinfunction "1_1") (pintype "passive"))
    )
    (net (code "23") (name "/DOZEN7") (class "Default")
      (node (ref "R7") (pin "1") (pinfunction "1_1") (pintype "passive"))
      (node (ref "SEC0") (pin "A") (pinfunction "A_A") (pintype "passive"))
      (node (ref "SEC10") (pin "A") (pinfunction "A_A") (pintype "passive"))
      (node (ref "SEC15") (pin "A") (pinfunction "A_A") (pintype "passive"))
      (node (ref "SEC20") (pin "A") (pinfunction "A_A") (pintype "passive"))
      (node (ref "SEC25") (pin "A") (pinfunction "A_A") (pintype "passive"))
      (node (ref "SEC30") (pin "A") (pinfunction "A_A") (pintype "passive"))
      (node (ref "SEC35") (pin "A") (pinfunction "A_A") (pintype "passive"))
      (node (ref "SEC40") (pin "A") (pinfunction "A_A") (pintype "passive"))
      (node (ref "SEC45") (pin "A") (pinfunction "A_A") (pintype "passive"))
      (node (ref "SEC5") (pin "A") (pinfunction "A_A") (pintype "passive"))
      (node (ref "SEC50") (pin "A") (pinfunction "A_A") (pintype "passive"))
      (node (ref "SEC55") (pin "A") (pinfunction "A_A") (pintype "passive"))
    )
    (net (code "24") (name "/DOZEN8") (class "Default")
      (node (ref "R8") (pin "1") (pinfunction "1_1") (pintype "passive"))
      (node (ref "SEC1") (pin "A") (pinfunction "A_A") (pintype "passive"))
      (node (ref "SEC11") (pin "A") (pinfunction "A_A") (pintype "passive"))
      (node (ref "SEC16") (pin "A") (pinfunction "A_A") (pintype "passive"))
      (node (ref "SEC21") (pin "A") (pinfunction "A_A") (pintype "passive"))
      (node (ref "SEC26") (pin "A") (pinfunction "A_A") (pintype "passive"))
      (node (ref "SEC31") (pin "A") (pinfunction "A_A") (pintype "passive"))
      (node (ref "SEC36") (pin "A") (pinfunction "A_A") (pintype "passive"))
      (node (ref "SEC41") (pin "A") (pinfunction "A_A") (pintype "passive"))
      (node (ref "SEC46") (pin "A") (pinfunction "A_A") (pintype "passive"))
      (node (ref "SEC51") (pin "A") (pinfunction "A_A") (pintype "passive"))
      (node (ref "SEC56") (pin "A") (pinfunction "A_A") (pintype "passive"))
      (node (ref "SEC6") (pin "A") (pinfunction "A_A") (pintype "passive"))
    )
    (net (code "25") (name "/DOZEN9") (class "Default")
      (node (ref "R9") (pin "1") (pinfunction "1_1") (pintype "passive"))
      (node (ref "SEC12") (pin "A") (pinfunction "A_A") (pintype "passive"))
      (node (ref "SEC17") (pin "A") (pinfunction "A_A") (pintype "passive"))
      (node (ref "SEC2") (pin "A") (pinfunction "A_A") (pintype "passive"))
      (node (ref "SEC22") (pin "A") (pinfunction "A_A") (pintype "passive"))
      (node (ref "SEC27") (pin "A") (pinfunction "A_A") (pintype "passive"))
      (node (ref "SEC32") (pin "A") (pinfunction "A_A") (pintype "passive"))
      (node (ref "SEC37") (pin "A") (pinfunction "A_A") (pintype "passive"))
      (node (ref "SEC42") (pin "A") (pinfunction "A_A") (pintype "passive"))
      (node (ref "SEC47") (pin "A") (pinfunction "A_A") (pintype "passive"))
      (node (ref "SEC52") (pin "A") (pinfunction "A_A") (pintype "passive"))
      (node (ref "SEC57") (pin "A") (pinfunction "A_A") (pintype "passive"))
      (node (ref "SEC7") (pin "A") (pinfunction "A_A") (pintype "passive"))
    )
    (net (code "26") (name "/DOZEN10") (class "Default")
      (node (ref "R10") (pin "1") (pinfunction "1_1") (pintype "passive"))
      (node (ref "SEC13") (pin "A") (pinfunction "A_A") (pintype "passive"))
      (node (ref "SEC18") (pin "A") (pinfunction "A_A") (pintype "passive"))
      (node (ref "SEC23") (pin "A") (pinfunction "A_A") (pintype "passive"))
      (node (ref "SEC28") (pin "A") (pinfunction "A_A") (pintype "passive"))
      (node (ref "SEC3") (pin "A") (pinfunction "A_A") (pintype "passive"))
      (node (ref "SEC33") (pin "A") (pinfunction "A_A") (pintype "passive"))
      (node (ref "SEC38") (pin "A") (pinfunction "A_A") (pintype "passive"))
      (node (ref "SEC43") (pin "A") (pinfunction "A_A") (pintype "passive"))
      (node (ref "SEC48") (pin "A") (pinfunction "A_A") (pintype "passive"))
      (node (ref "SEC53") (pin "A") (pinfunction "A_A") (pintype "passive"))
      (node (ref "SEC58") (pin "A") (pinfunction "A_A") (pintype "passive"))
      (node (ref "SEC8") (pin "A") (pinfunction "A_A") (pintype "passive"))
    )
    (net (code "27") (name "/DOZEN11") (class "Default")
      (node (ref "R11") (pin "1") (pinfunction "1_1") (pintype "passive"))
      (node (ref "SEC14") (pin "A") (pinfunction "A_A") (pintype "passive"))
      (node (ref "SEC19") (pin "A") (pinfunction "A_A") (pintype "passive"))
      (node (ref "SEC24") (pin "A") (pinfunction "A_A") (pintype "passive"))
      (node (ref "SEC29") (pin "A") (pinfunction "A_A") (pintype "passive"))
      (node (ref "SEC34") (pin "A") (pinfunction "A_A") (pintype "passive"))
      (node (ref "SEC39") (pin "A") (pinfunction "A_A") (pintype "passive"))
      (node (ref "SEC4") (pin "A") (pinfunction "A_A") (pintype "passive"))
      (node (ref "SEC44") (pin "A") (pinfunction "A_A") (pintype "passive"))
      (node (ref "SEC49") (pin "A") (pinfunction "A_A") (pintype "passive"))
      (node (ref "SEC54") (pin "A") (pinfunction "A_A") (pintype "passive"))
      (node (ref "SEC59") (pin "A") (pinfunction "A_A") (pintype "passive"))
      (node (ref "SEC9") (pin "A") (pinfunction "A_A") (pintype "passive"))
    )
    (net (code "28") (name "/DOZEN12") (class "Default")
      (node (ref "R12") (pin "1") (pinfunction "1_1") (pintype "passive"))
      (node (ref "SPECIAL0") (pin "A") (pinfunction "A_A") (pintype "passive"))
      (node (ref "SPECIAL11") (pin "A") (pinfunction "A_A") (pintype "passive"))
      (node (ref "SPECIAL3") (pin "A") (pinfunction "A_A") (pintype "passive"))
      (node (ref "SPECIAL5") (pin "A") (pinfunction "A_A") (pintype "passive"))
      (node (ref "SPECIAL6") (pin "A") (pinfunction "A_A") (pintype "passive"))
      (node (ref "SPECIAL9") (pin "A") (pinfunction "A_A") (pintype "passive"))
    )
    (net (code "29") (name "/LIGHT_SENSOR") (class "Default")
      (node (ref "R27") (pin "2") (pinfunction "2_2") (pintype "passive"))
      (node (ref "U$1") (pin "8") (pinfunction "PC0_8") (pintype "bidirectional"))
      (node (ref "U$11") (pin "1") (pinfunction "COL_1") (pintype "passive"))
    )
    (net (code "30") (name "/RST") (class "Default")
      (node (ref "R16") (pin "1") (pinfunction "1_1") (pintype "passive"))
      (node (ref "U$1") (pin "7") (pinfunction "NRST_7") (pintype "input"))
    )
    (net (code "31") (name "/SPI1_MISO") (class "Default")
      (node (ref "U$1") (pin "22") (pinfunction "PA6_22") (pintype "bidirectional"))
      (node (ref "U2") (pin "12") (pinfunction "SDO_12") (pintype "bidirectional"))
    )
    (net (code "32") (name "/SPI1_MOSI") (class "Default")
      (node (ref "U$1") (pin "23") (pinfunction "PA7_23") (pintype "bidirectional"))
      (node (ref "U2") (pin "13") (pinfunction "SDA_13") (pintype "bidirectional"))
    )
    (net (code "33") (name "/SPI1_NSS") (class "Default")
      (node (ref "U$1") (pin "20") (pinfunction "PA4_20") (pintype "bidirectional"))
      (node (ref "U2") (pin "7") (pinfunction "CS_7") (pintype "bidirectional"))
    )
    (net (code "34") (name "/SPI1_SCK") (class "Default")
      (node (ref "U$1") (pin "21") (pinfunction "PA5_21") (pintype "bidirectional"))
      (node (ref "U2") (pin "14") (pinfunction "SCL_14") (pintype "bidirectional"))
    )
    (net (code "35") (name "/TCK") (class "Default")
      (node (ref "PROG") (pin "P$2") (pinfunction "2_P$2") (pintype "passive"))
      (node (ref "R23") (pin "2") (pinfunction "2_2") (pintype "passive"))
      (node (ref "U$1") (pin "49") (pinfunction "PA14_49") (pintype "bidirectional"))
    )
    (net (code "36") (name "/TDO") (class "Default")
      (node (ref "PROG") (pin "P$6") (pinfunction "6_P$6") (pintype "passive"))
      (node (ref "R36") (pin "2") (pinfunction "2_2") (pintype "passive"))
      (node (ref "U$1") (pin "55") (pinfunction "PB3_55") (pintype "bidirectional"))
    )
    (net (code "37") (name "/TMS") (class "Default")
      (node (ref "PROG") (pin "P$4") (pinfunction "4_P$4") (pintype "passive"))
      (node (ref "R31") (pin "2") (pinfunction "2_2") (pintype "passive"))
      (node (ref "U$1") (pin "46") (pinfunction "PA13_46") (pintype "bidirectional"))
    )
    (net (code "38") (name "/TOUCH1") (class "Default")
      (node (ref "U$1") (pin "50") (pinfunction "PA15_50") (pintype "bidirectional"))
    )
    (net (code "39") (name "/TOUCH2") (class "Default")
      (node (ref "U$1") (pin "11") (pinfunction "PC3_11") (pintype "bidirectional"))
    )
    (net (code "40") (name "/TOUCH3") (class "Default")
      (node (ref "U$1") (pin "24") (pinfunction "PC4_24") (pintype "bidirectional"))
    )
    (net (code "41") (name "/TOUCH4") (class "Default")
      (node (ref "U$1") (pin "54") (pinfunction "PD2_54") (pintype "bidirectional"))
    )
    (net (code "42") (name "/TOUCH5") (class "Default")
      (node (ref "U$1") (pin "57") (pinfunction "PB5_57") (pintype "input"))
    )
    (net (code "43") (name "/TRST") (class "Default")
      (node (ref "PROG") (pin "P$5") (pinfunction "5_P$5") (pintype "passive"))
      (node (ref "R43") (pin "2") (pinfunction "2_2") (pintype "passive"))
      (node (ref "U$1") (pin "56") (pinfunction "PB4_56") (pintype "bidirectional"))
    )
    (net (code "44") (name "/USART1_RX") (class "Default")
      (node (ref "FTDI") (pin "3") (pinfunction "3_3") (pintype "passive"))
      (node (ref "U$1") (pin "43") (pinfunction "PA10_43") (pintype "bidirectional"))
    )
    (net (code "45") (name "/USART1_TX") (class "Default")
      (node (ref "FTDI") (pin "2") (pinfunction "2_2") (pintype "passive"))
      (node (ref "U$1") (pin "42") (pinfunction "PA9_42") (pintype "input"))
    )
    (net (code "46") (name "/USB_DISCONNECT") (class "Default")
      (node (ref "Q7") (pin "1") (pinfunction "G_1") (pintype "passive"))
      (node (ref "R34") (pin "2") (pinfunction "2_2") (pintype "passive"))
      (node (ref "U$1") (pin "41") (pinfunction "PA8_41") (pintype "bidirectional"))
    )
    (net (code "47") (name "/USB_DM") (class "Default")
      (node (ref "R28") (pin "1") (pinfunction "1_1") (pintype "passive"))
      (node (ref "U$1") (pin "44") (pinfunction "PA11_44") (pintype "bidirectional"))
    )
    (net (code "48") (name "/USB_DP") (class "Default")
      (node (ref "R29") (pin "1") (pinfunction "1_1") (pintype "passive"))
      (node (ref "R30") (pin "2") (pinfunction "2_2") (pintype "passive"))
      (node (ref "U$1") (pin "45") (pinfunction "PA12_45") (pintype "bidirectional"))
    )
    (net (code "49") (name "/WAKE") (class "Default")
      (node (ref "Q1") (pin "1") (pinfunction "G_1") (pintype "passive"))
      (node (ref "U$1") (pin "2") (pinfunction "PC13-TAMPER-RTC_2") (pintype "input"))
    )
    (net (code "50") (name "GND") (class "Default")
      (node (ref "C1") (pin "2") (pinfunction "2_2") (pintype "passive"))
      (node (ref "C11") (pin "2") (pinfunction "2_2") (pintype "passive"))
      (node (ref "C17") (pin "2") (pinfunction "2_2") (pintype "passive"))
      (node (ref "C18") (pin "2") (pinfunction "2_2") (pintype "passive"))
      (node (ref "C2") (pin "2") (pinfunction "2_2") (pintype "passive"))
      (node (ref "C20") (pin "2") (pinfunction "2_2") (pintype "passive"))
      (node (ref "C23") (pin "2") (pinfunction "2_2") (pintype "passive"))
      (node (ref "C24") (pin "-") (pinfunction "-_-") (pintype "passive"))
      (node (ref "C25") (pin "-") (pinfunction "-_-") (pintype "passive"))
      (node (ref "C27") (pin "2") (pinfunction "2_2") (pintype "passive"))
      (node (ref "C3") (pin "2") (pinfunction "2_2") (pintype "passive"))
      (node (ref "C4") (pin "2") (pinfunction "2_2") (pintype "passive"))
      (node (ref "C5") (pin "2") (pinfunction "2_2") (pintype "passive"))
      (node (ref "C6") (pin "1") (pinfunction "1_1") (pintype "passive"))
      (node (ref "C7") (pin "2") (pinfunction "2_2") (pintype "passive"))
      (node (ref "C8") (pin "2") (pinfunction "2_2") (pintype "passive"))
      (node (ref "FTDI") (pin "5") (pinfunction "5_5") (pintype "passive"))
      (node (ref "FTDI") (pin "6") (pinfunction "6_6") (pintype "passive"))
      (node (ref "IC1") (pin "1") (pinfunction "ADJ_1") (pintype "input"))
      (node (ref "PROG") (pin "P$3") (pinfunction "3_P$3") (pintype "passive"))
      (node (ref "Q1") (pin "2") (pinfunction "S_2") (pintype "passive"))
      (node (ref "R33") (pin "1") (pinfunction "1_1") (pintype "passive"))
      (node (ref "U$1") (pin "12") (pinfunction "VSS_A_12") (pintype "power_in"))
      (node (ref "U$1") (pin "18") (pinfunction "VSS_4_18") (pintype "power_in"))
      (node (ref "U$1") (pin "28") (pinfunction "PB2_28") (pintype "bidirectional"))
      (node (ref "U$1") (pin "31") (pinfunction "VSS_1_31") (pintype "power_in"))
      (node (ref "U$1") (pin "47") (pinfunction "VSS_2_47") (pintype "power_in"))
      (node (ref "U$1") (pin "60") (pinfunction "BOOT0_60") (pintype "input"))
      (node (ref "U$1") (pin "63") (pinfunction "VSS_3_63") (pintype "power_in"))
      (node (ref "U$11") (pin "2") (pinfunction "EMI_2") (pintype "passive"))
      (node (ref "U$12") (pin "GND") (pinfunction "GND_GND") (pintype "bidirectional"))
      (node (ref "U$12") (pin "MTN1") (pinfunction "MTN2_MTN1") (pintype "bidirectional"))
      (node (ref "U$12") (pin "MTN2") (pinfunction "MTN3_MTN2") (pintype "bidirectional"))
      (node (ref "U$12") (pin "MTN3") (pinfunction "MTN1_MTN3") (pintype "bidirectional"))
      (node (ref "U$12") (pin "MTN4") (pinfunction "MTN4_MTN4") (pintype "bidirectional"))
      (node (ref "U$13") (pin "2") (pinfunction "GND_2") (pintype "bidirectional"))
      (node (ref "U2") (pin "2") (pinfunction "GND_2") (pintype "bidirectional"))
      (node (ref "U2") (pin "4") (pinfunction "GND_4") (pintype "bidirectional"))
      (node (ref "U2") (pin "5") (pinfunction "GND_5") (pintype "bidirectional"))
      (node (ref "Y1") (pin "2") (pinfunction "2_2") (pintype "passive"))
    )
    (net (code "51") (name "Net-(C6-Pad2)") (class "Default")
      (node (ref "C6") (pin "2") (pinfunction "2_2") (pintype "passive"))
      (node (ref "R13") (pin "1") (pinfunction "1_1") (pintype "passive"))
      (node (ref "U$2") (pin "P$4") (pinfunction "P$4_P$4") (pintype "bidirectional"))
    )
    (net (code "52") (name "Net-(FTDI-Pad4)") (class "Default")
      (node (ref "FTDI") (pin "4") (pinfunction "4_4") (pintype "passive"))
      (node (ref "JP1") (pin "1") (pinfunction "1_1") (pintype "passive"))
    )
    (net (code "53") (name "Net-(JP2-Pad2)") (class "Default")
      (node (ref "JP2") (pin "2") (pinfunction "2_2") (pintype "passive"))
      (node (ref "U$12") (pin "VBUS") (pinfunction "VBUS_VBUS") (pintype "bidirectional"))
    )
    (net (code "54") (name "Net-(Q1-D)") (class "Default")
      (node (ref "FTDI") (pin "1") (pinfunction "1_1") (pintype "passive"))
      (node (ref "Q1") (pin "3") (pinfunction "D_3") (pintype "passive"))
    )
    (net (code "55") (name "Net-(Q6-G)") (class "Default")
      (node (ref "Q6") (pin "1") (pinfunction "G_1") (pintype "passive"))
      (node (ref "Q7") (pin "3") (pinfunction "D_3") (pintype "passive"))
      (node (ref "R32") (pin "1") (pinfunction "1_1") (pintype "passive"))
    )
    (net (code "56") (name "Net-(Q6-S)") (class "Default")
      (node (ref "Q6") (pin "2") (pinfunction "S_2") (pintype "passive"))
      (node (ref "R30") (pin "1") (pinfunction "1_1") (pintype "passive"))
    )
    (net (code "57") (name "Net-(Q7-S)") (class "Default")
      (node (ref "Q7") (pin "2") (pinfunction "S_2") (pintype "passive"))
      (node (ref "R33") (pin "2") (pinfunction "2_2") (pintype "passive"))
    )
    (net (code "58") (name "Net-(U$1-PB10)") (class "Default")
      (node (ref "R1") (pin "2") (pinfunction "2_2") (pintype "passive"))
      (node (ref "U$1") (pin "29") (pinfunction "PB10_29") (pintype "input"))
    )
    (net (code "59") (name "Net-(U$1-PB11)") (class "Default")
      (node (ref "R2") (pin "2") (pinfunction "2_2") (pintype "passive"))
      (node (ref "U$1") (pin "30") (pinfunction "PB11_30") (pintype "input"))
    )
    (net (code "60") (name "Net-(U$1-PB12)") (class "Default")
      (node (ref "R3") (pin "2") (pinfunction "2_2") (pintype "passive"))
      (node (ref "U$1") (pin "33") (pinfunction "PB12_33") (pintype "input"))
    )
    (net (code "61") (name "Net-(U$1-PB13)") (class "Default")
      (node (ref "R4") (pin "2") (pinfunction "2_2") (pintype "passive"))
      (node (ref "U$1") (pin "34") (pinfunction "PB13_34") (pintype "input"))
    )
    (net (code "62") (name "Net-(U$1-PB14)") (class "Default")
      (node (ref "R5") (pin "2") (pinfunction "2_2") (pintype "passive"))
      (node (ref "U$1") (pin "35") (pinfunction "PB14_35") (pintype "input"))
    )
    (net (code "63") (name "Net-(U$1-PB15)") (class "Default")
      (node (ref "R6") (pin "2") (pinfunction "2_2") (pintype "passive"))
      (node (ref "U$1") (pin "36") (pinfunction "PB15_36") (pintype "input"))
    )
    (net (code "64") (name "Net-(U$1-PC5)") (class "Default")
      (node (ref "R12") (pin "2") (pinfunction "2_2") (pintype "passive"))
      (node (ref "U$1") (pin "25") (pinfunction "PC5_25") (pintype "bidirectional"))
    )
    (net (code "65") (name "Net-(U$1-PC8)") (class "Default")
      (node (ref "R8") (pin "2") (pinfunction "2_2") (pintype "passive"))
      (node (ref "U$1") (pin "39") (pinfunction "PC8_39") (pintype "bidirectional"))
    )
    (net (code "66") (name "Net-(U$1-PC9)") (class "Default")
      (node (ref "R7") (pin "2") (pinfunction "2_2") (pintype "passive"))
      (node (ref "U$1") (pin "40") (pinfunction "PC9_40") (pintype "bidirectional"))
    )
    (net (code "67") (name "Net-(U$1-PC10)") (class "Default")
      (node (ref "R11") (pin "2") (pinfunction "2_2") (pintype "passive"))
      (node (ref "U$1") (pin "51") (pinfunction "PC10_51") (pintype "bidirectional"))
    )
    (net (code "68") (name "Net-(U$1-PC11)") (class "Default")
      (node (ref "R10") (pin "2") (pinfunction "2_2") (pintype "passive"))
      (node (ref "U$1") (pin "52") (pinfunction "PC11_52") (pintype "bidirectional"))
    )
    (net (code "69") (name "Net-(U$1-PC12)") (class "Default")
      (node (ref "R9") (pin "2") (pinfunction "2_2") (pintype "passive"))
      (node (ref "U$1") (pin "53") (pinfunction "PC12_53") (pintype "bidirectional"))
    )
    (net (code "70") (name "Net-(U$1-PC14-OSC32_IN)") (class "Default")
      (node (ref "C7") (pin "1") (pinfunction "1_1") (pintype "passive"))
      (node (ref "U$1") (pin "3") (pinfunction "PC14-OSC32_IN_3") (pintype "input"))
      (node (ref "U$2") (pin "P$1") (pinfunction "P$1_P$1") (pintype "bidirectional"))
    )
    (net (code "71") (name "Net-(U$1-PC15-OSC32_OUT)") (class "Default")
      (node (ref "R13") (pin "2") (pinfunction "2_2") (pintype "passive"))
      (node (ref "U$1") (pin "4") (pinfunction "PC15-OSC32_OUT_4") (pintype "input"))
    )
    (net (code "72") (name "Net-(U$1-PD0-OSC_IN)") (class "Default")
      (node (ref "U$1") (pin "5") (pinfunction "PD0-OSC_IN_5") (pintype "input"))
      (node (ref "Y1") (pin "1") (pinfunction "1_1") (pintype "passive"))
    )
    (net (code "73") (name "Net-(U$1-PD1-OSC_OUT)") (class "Default")
      (node (ref "U$1") (pin "6") (pinfunction "PD1-OSC_OUT_6") (pintype "input"))
      (node (ref "Y1") (pin "3") (pinfunction "3_3") (pintype "passive"))
    )
    (net (code "74") (name "Net-(U$13-IO1_IN)") (class "Default")
      (node (ref "U$12") (pin "D-") (pinfunction "D-_D-") (pintype "bidirectional"))
      (node (ref "U$13") (pin "1") (pinfunction "IO1_IN_1") (pintype "bidirectional"))
    )
    (net (code "75") (name "Net-(U$13-IO1_OUT)") (class "Default")
      (node (ref "R28") (pin "2") (pinfunction "2_2") (pintype "passive"))
      (node (ref "U$13") (pin "6") (pinfunction "IO1_OUT_6") (pintype "bidirectional"))
    )
    (net (code "76") (name "Net-(U$13-IO2_IN)") (class "Default")
      (node (ref "U$12") (pin "D+") (pinfunction "D+_D+") (pintype "bidirectional"))
      (node (ref "U$13") (pin "3") (pinfunction "IO2_IN_3") (pintype "bidirectional"))
    )
    (net (code "77") (name "Net-(U$13-IO2_OUT)") (class "Default")
      (node (ref "R29") (pin "2") (pinfunction "2_2") (pintype "passive"))
      (node (ref "U$13") (pin "4") (pinfunction "IO2_OUT_4") (pintype "bidirectional"))
    )
    (net (code "78") (name "unconnected-(U$2-PadP$2)") (class "Default")
      (node (ref "U$2") (pin "P$2") (pinfunction "P$2_P$2") (pintype "bidirectional"))
    )
    (net (code "79") (name "unconnected-(U$2-PadP$3)") (class "Default")
      (node (ref "U$2") (pin "P$3") (pinfunction "P$3_P$3") (pintype "bidirectional"))
    )
    (net (code "80") (name "unconnected-(U$12-PadID)") (class "Default")
      (node (ref "U$12") (pin "ID") (pinfunction "ID_ID") (pintype "bidirectional"))
    )
    (net (code "81") (name "unconnected-(U2-NC-Pad3)") (class "Default")
      (node (ref "U2") (pin "3") (pinfunction "NC_3") (pintype "bidirectional"))
    )
    (net (code "82") (name "unconnected-(U2-NC-Pad10)") (class "Default")
      (node (ref "U2") (pin "10") (pinfunction "NC_10") (pintype "bidirectional"))
    )
    (net (code "83") (name "unconnected-(U2-NC-Pad11)") (class "Default")
      (node (ref "U2") (pin "11") (pinfunction "NC_11") (pintype "bidirectional"))
    )
  )
)
